# gyrotestbench.net
KiCad netlist of a schematic drawn in EAGLE
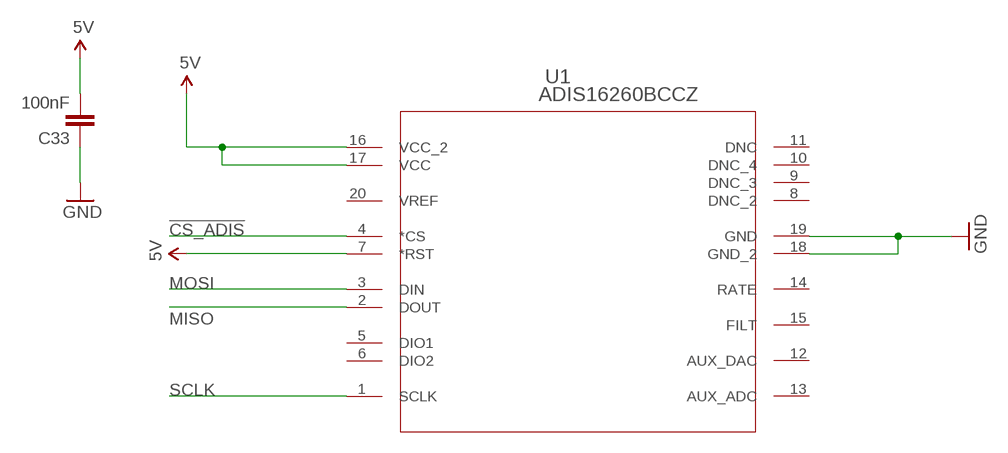
[diagram p0: schematic, sheet 1]
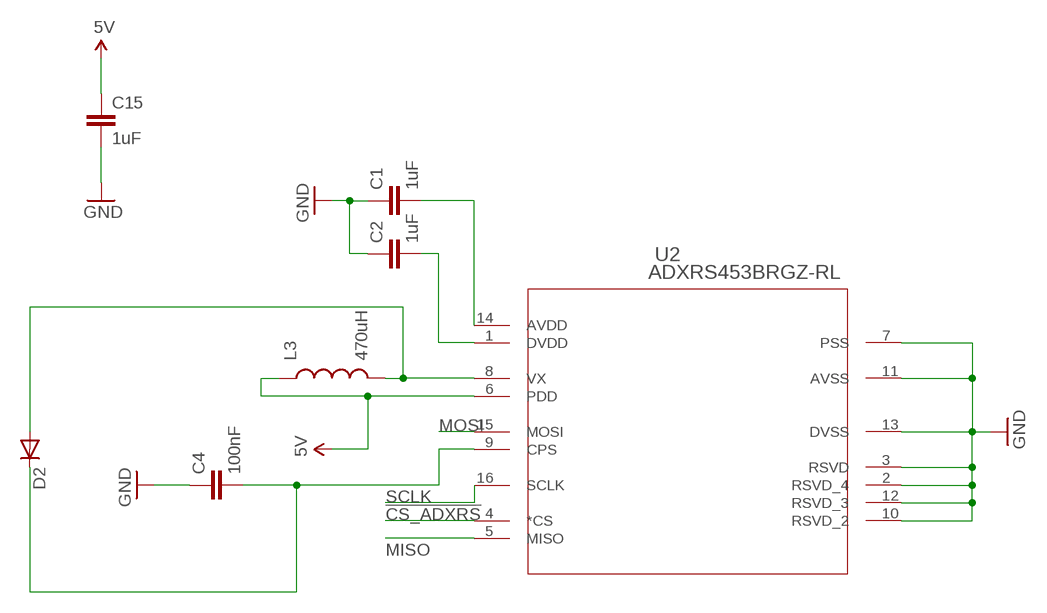
[diagram p1: schematic, sheet 2]
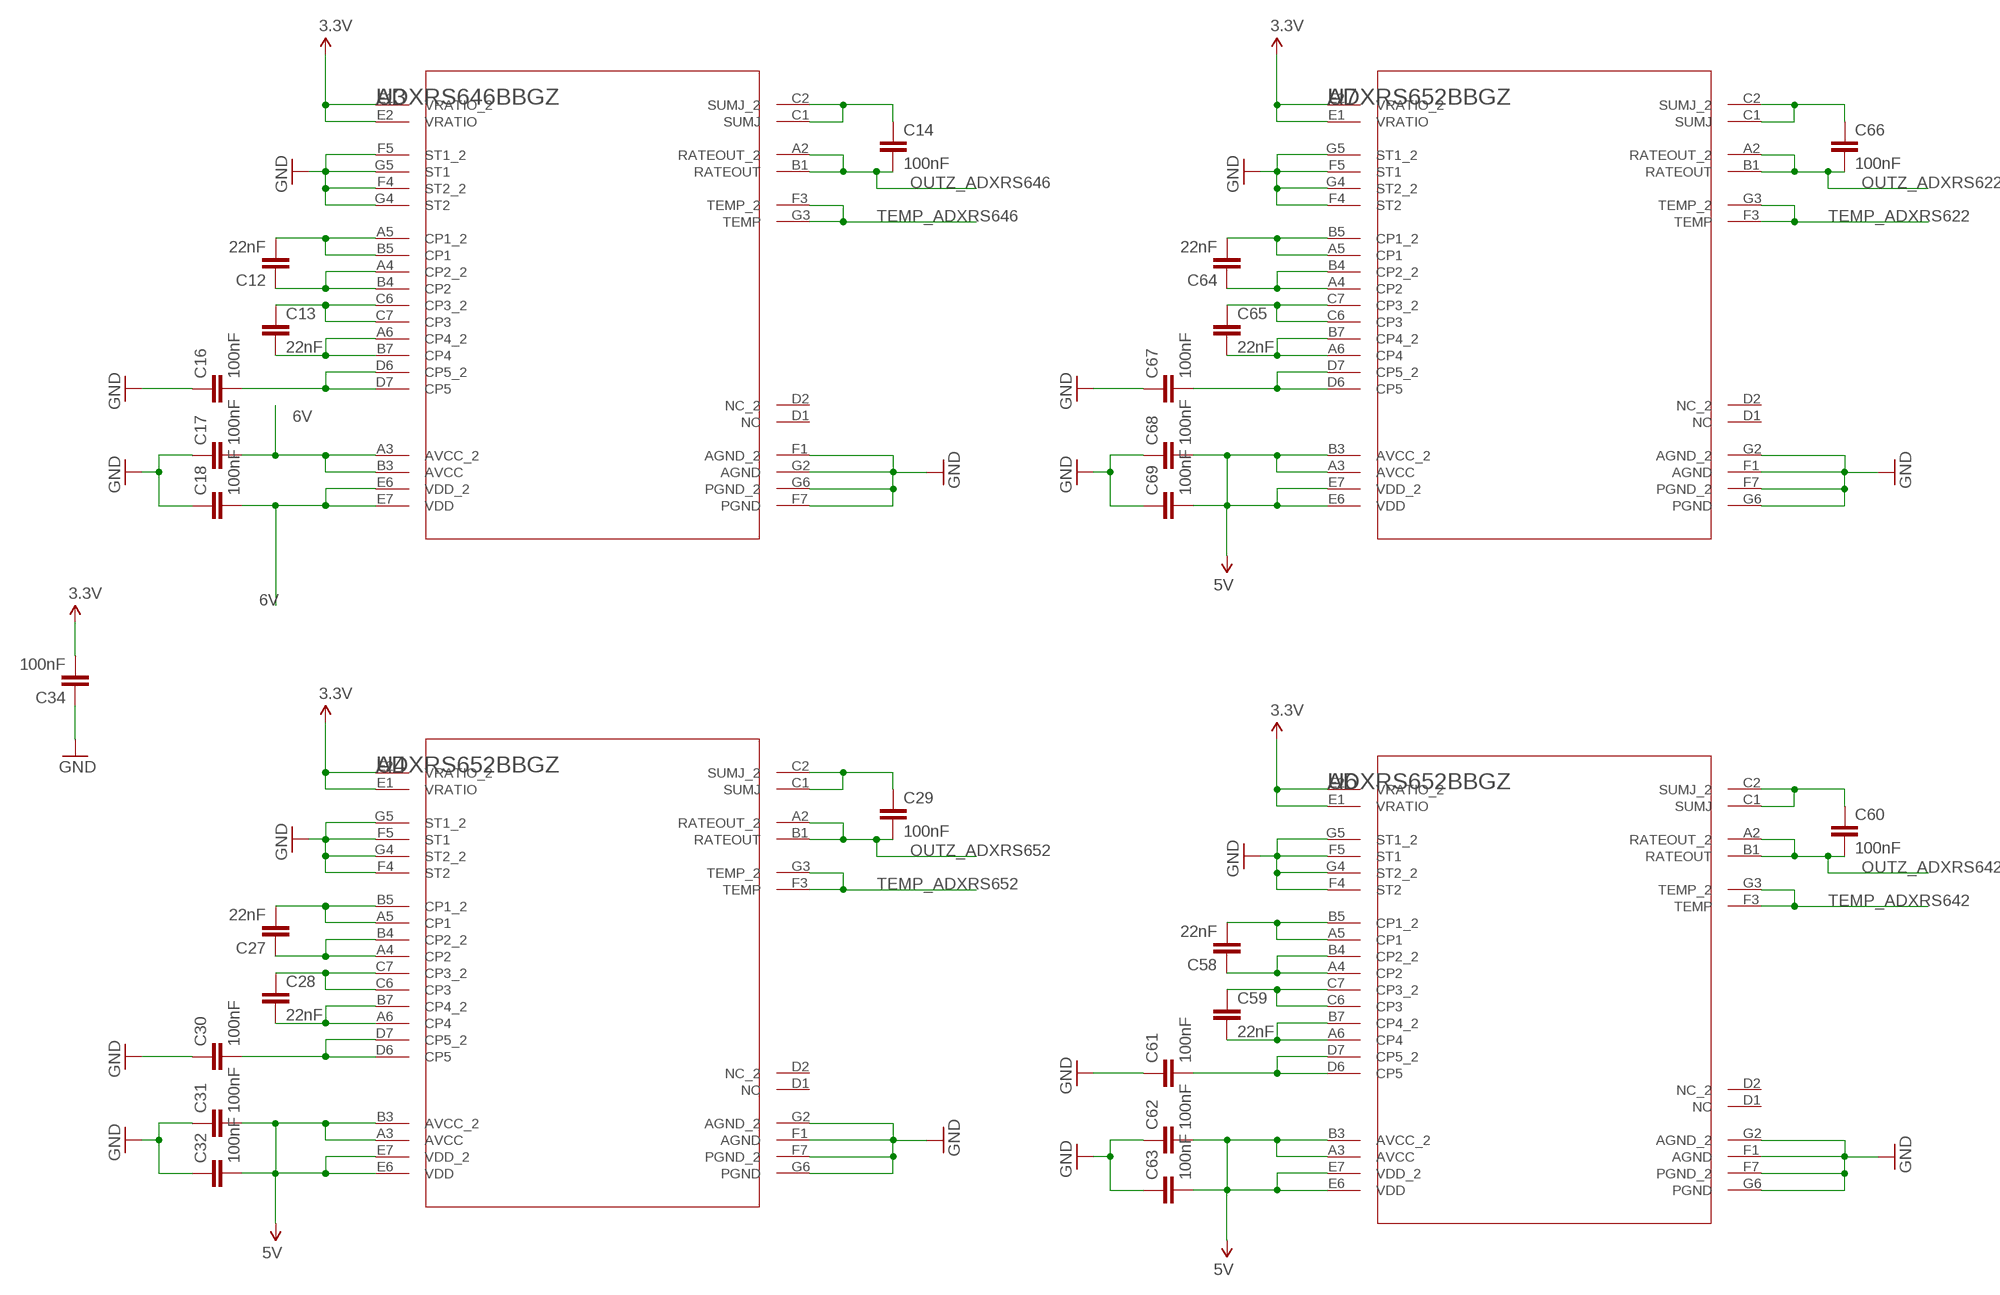
[diagram p2: schematic, sheet 3]
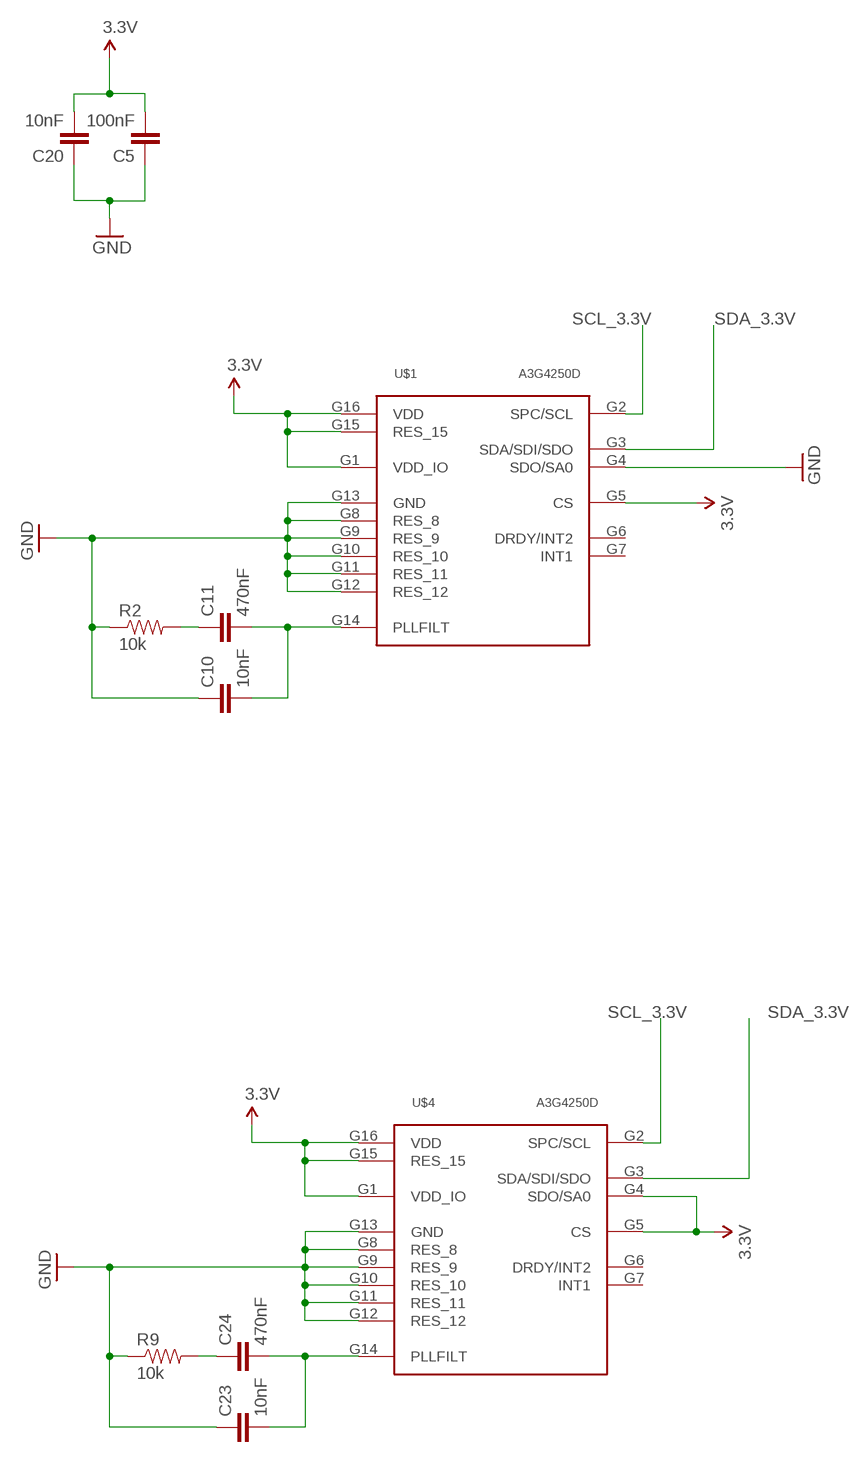
[diagram p3: schematic, sheet 4]
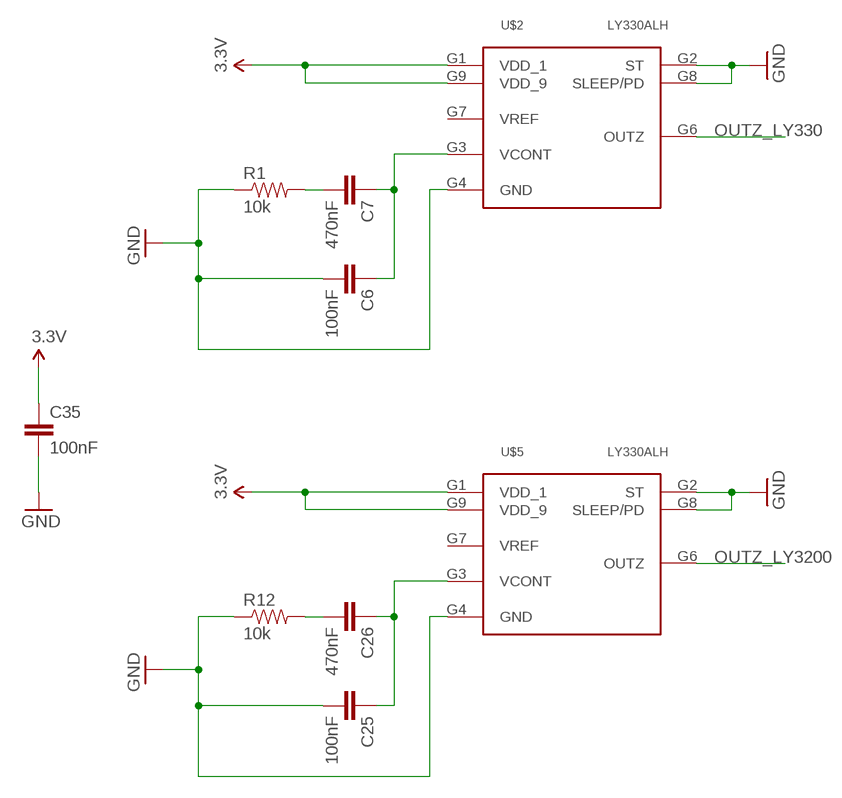
[diagram p4: schematic, sheet 5]
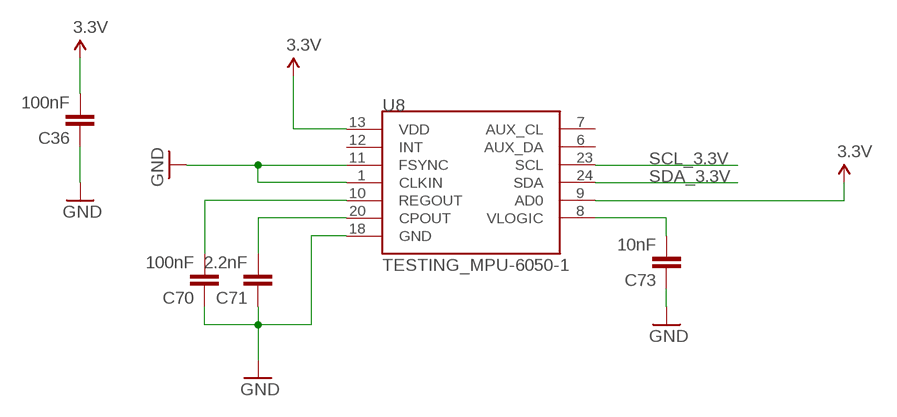
[diagram p5: schematic, sheet 6]
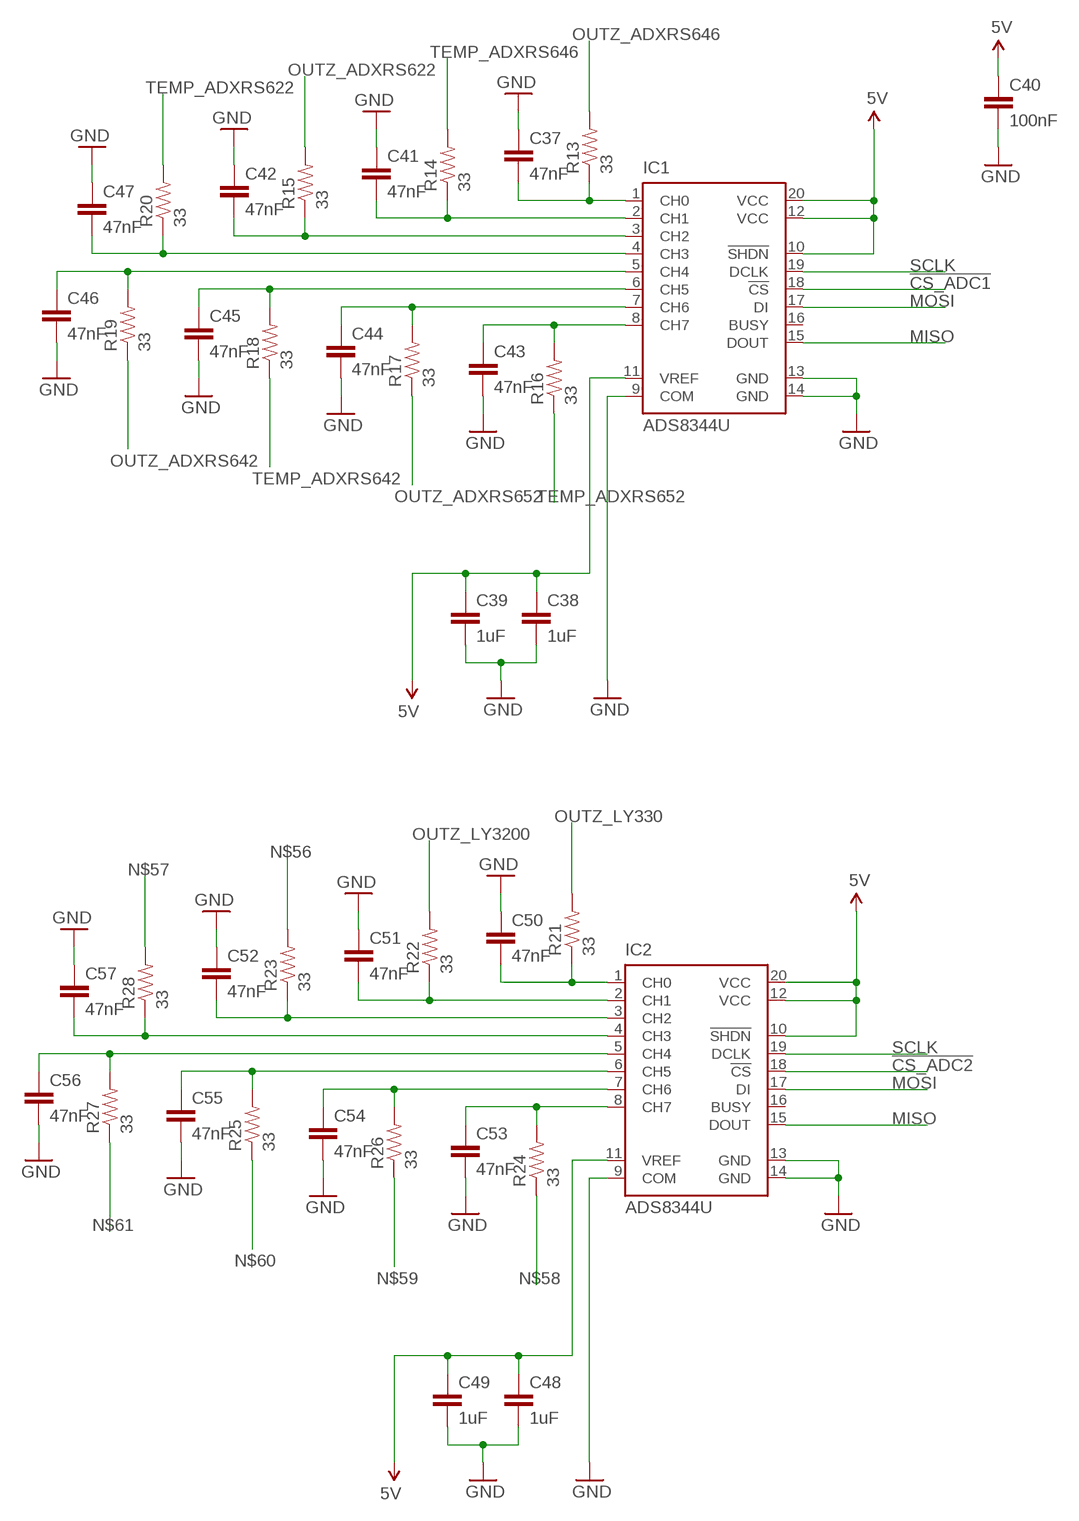
[diagram p6: schematic, sheet 7]
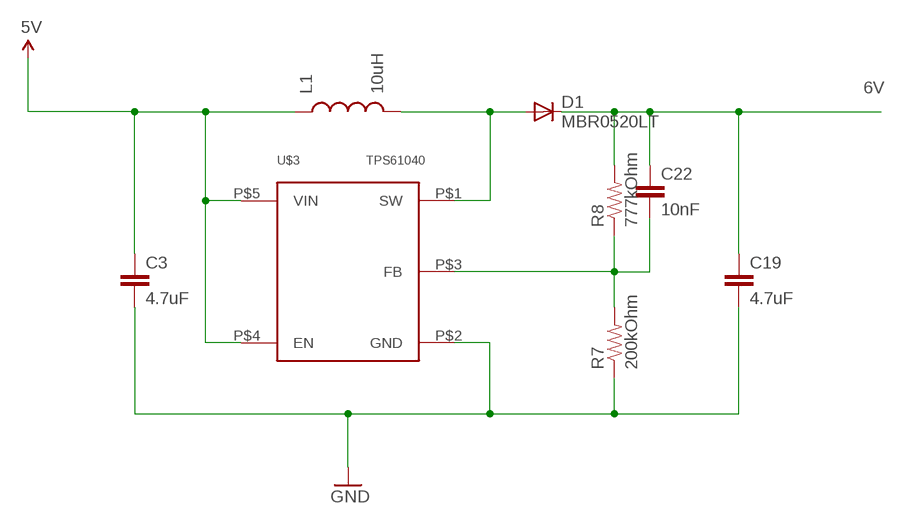
[diagram p7: schematic, sheet 8]
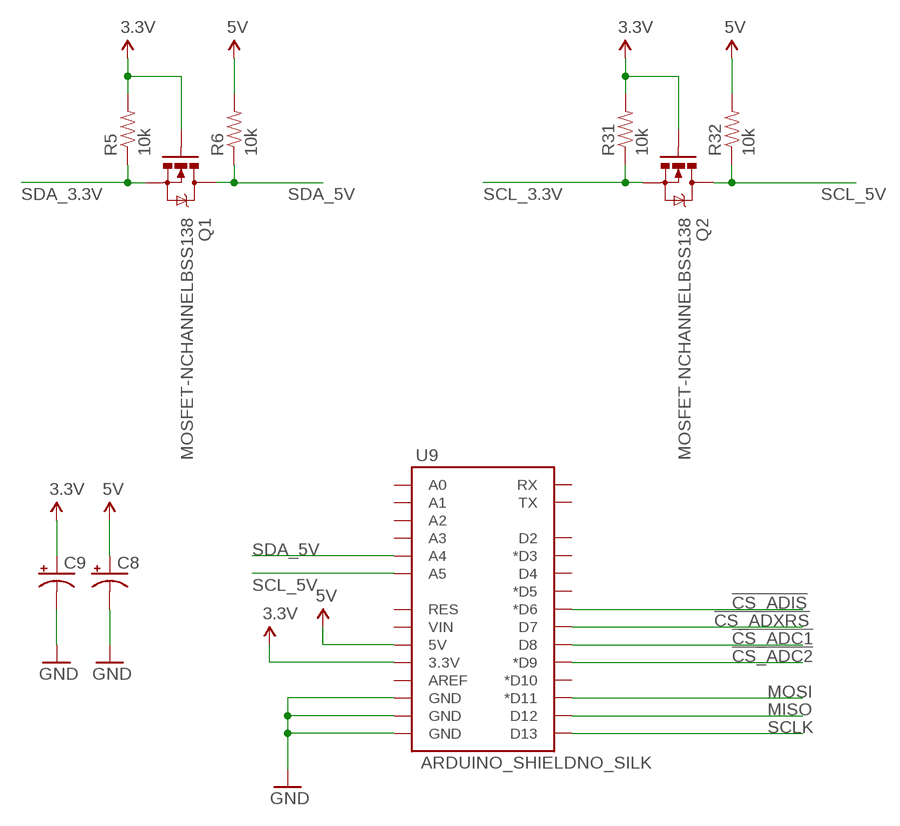
[diagram p8: schematic, sheet 9]

(export (version "E")
  (design (tool "Eeschema 10.0.6"))
  (components
    (comp (ref "C5")
      (value "100nF")
      (footprint "eagle-import:0603-CAP")
      (libsource (lib "eagle-import") (part "CAP0603-CAP"))
    )
    (comp (ref "C10")
      (value "10nF")
      (footprint "eagle-import:0603-CAP")
      (libsource (lib "eagle-import") (part "CAP0603-CAP"))
    )
    (comp (ref "C11")
      (value "470nF")
      (footprint "eagle-import:0603-CAP")
      (libsource (lib "eagle-import") (part "CAP0603-CAP"))
    )
    (comp (ref "C20")
      (value "10nF")
      (footprint "eagle-import:0603-CAP")
      (libsource (lib "eagle-import") (part "CAP0603-CAP"))
    )
    (comp (ref "C23")
      (value "10nF")
      (footprint "eagle-import:0603-CAP")
      (libsource (lib "eagle-import") (part "CAP0603-CAP"))
    )
    (comp (ref "C24")
      (value "470nF")
      (footprint "eagle-import:0603-CAP")
      (libsource (lib "eagle-import") (part "CAP0603-CAP"))
    )
    (comp (ref "R2")
      (value "10k")
      (footprint "eagle-import:0603-RES")
      (libsource (lib "eagle-import") (part "RESISTOR0603-RES"))
    )
    (comp (ref "R9")
      (value "10k")
      (footprint "eagle-import:0603-RES")
      (libsource (lib "eagle-import") (part "RESISTOR0603-RES"))
    )
    (comp (ref "U$1")
      (value "A3G4250D")
      (footprint "eagle-import:LGA-16")
      (libsource (lib "eagle-import") (part "A3G4250D"))
    )
    (comp (ref "U$4")
      (value "A3G4250D")
      (footprint "eagle-import:LGA-16")
      (libsource (lib "eagle-import") (part "A3G4250D"))
    )
    (comp (ref "C8")
      (value "CPOL-USB")
      (footprint "eagle-import:PANASONIC_B")
      (libsource (lib "eagle-import") (part "CPOL-USB"))
    )
    (comp (ref "C9")
      (value "CPOL-USB")
      (footprint "eagle-import:PANASONIC_B")
      (libsource (lib "eagle-import") (part "CPOL-USB"))
    )
    (comp (ref "Q1")
      (value "MOSFET-NCHANNELBSS138")
      (footprint "eagle-import:SOT23")
      (libsource (lib "eagle-import") (part "MOSFET-NCHANNELBSS138"))
    )
    (comp (ref "Q2")
      (value "MOSFET-NCHANNELBSS138")
      (footprint "eagle-import:SOT23")
      (libsource (lib "eagle-import") (part "MOSFET-NCHANNELBSS138"))
    )
    (comp (ref "R5")
      (value "10k")
      (footprint "eagle-import:0603-RES")
      (libsource (lib "eagle-import") (part "RESISTOR0603-RES"))
    )
    (comp (ref "R6")
      (value "10k")
      (footprint "eagle-import:0603-RES")
      (libsource (lib "eagle-import") (part "RESISTOR0603-RES"))
    )
    (comp (ref "R31")
      (value "10k")
      (footprint "eagle-import:0603-RES")
      (libsource (lib "eagle-import") (part "RESISTOR0603-RES"))
    )
    (comp (ref "R32")
      (value "10k")
      (footprint "eagle-import:0603-RES")
      (libsource (lib "eagle-import") (part "RESISTOR0603-RES"))
    )
    (comp (ref "U9")
      (value "ARDUINO_SHIELDNO_SILK")
      (footprint "eagle-import:DUEMILANOVE_VIAS")
      (libsource (lib "eagle-import") (part "ARDUINO_SHIELDNO_SILK"))
    )
    (comp (ref "C1")
      (value "1uF")
      (footprint "eagle-import:0603-CAP")
      (libsource (lib "eagle-import") (part "CAP0603-CAP"))
    )
    (comp (ref "C2")
      (value "1uF")
      (footprint "eagle-import:0603-CAP")
      (libsource (lib "eagle-import") (part "CAP0603-CAP"))
    )
    (comp (ref "C4")
      (value "100nF")
      (footprint "eagle-import:0603-CAP")
      (libsource (lib "eagle-import") (part "CAP0603-CAP"))
    )
    (comp (ref "C15")
      (value "1uF")
      (footprint "eagle-import:0603-CAP")
      (libsource (lib "eagle-import") (part "CAP0603-CAP"))
    )
    (comp (ref "D2")
      (value "DIODEPTH")
      (footprint "eagle-import:DIODE-1N4001")
      (libsource (lib "eagle-import") (part "DIODEPTH"))
    )
    (comp (ref "L3")
      (value "470uH")
      (footprint "eagle-import:1210")
      (libsource (lib "eagle-import") (part "INDUCTOR1210"))
    )
    (comp (ref "U2")
      (value "ADXRS453BRGZ-RL")
      (footprint "eagle-import:RG_16_1")
      (libsource (lib "eagle-import") (part "ADXRS453BRGZ-RL"))
    )
    (comp (ref "C36")
      (value "100nF")
      (footprint "eagle-import:0603-CAP")
      (libsource (lib "eagle-import") (part "CAP0603-CAP"))
    )
    (comp (ref "C70")
      (value "100nF")
      (footprint "eagle-import:0603-CAP")
      (libsource (lib "eagle-import") (part "CAP0603-CAP"))
    )
    (comp (ref "C71")
      (value "2.2nF")
      (footprint "eagle-import:0603-CAP")
      (libsource (lib "eagle-import") (part "CAP0603-CAP"))
    )
    (comp (ref "C73")
      (value "10nF")
      (footprint "eagle-import:0603-CAP")
      (libsource (lib "eagle-import") (part "CAP0603-CAP"))
    )
    (comp (ref "U8")
      (value "TESTING_MPU-6050-1")
      (footprint "eagle-import:TESTING_QFN-24-4MM2")
      (libsource (lib "eagle-import") (part "TESTING_MPU-6050-1"))
    )
    (comp (ref "C37")
      (value "47nF")
      (footprint "eagle-import:0603-CAP")
      (libsource (lib "eagle-import") (part "CAP0603-CAP"))
    )
    (comp (ref "C38")
      (value "1uF")
      (footprint "eagle-import:0603-CAP")
      (libsource (lib "eagle-import") (part "CAP0603-CAP"))
    )
    (comp (ref "C39")
      (value "1uF")
      (footprint "eagle-import:0603-CAP")
      (libsource (lib "eagle-import") (part "CAP0603-CAP"))
    )
    (comp (ref "C40")
      (value "100nF")
      (footprint "eagle-import:0603-CAP")
      (libsource (lib "eagle-import") (part "CAP0603-CAP"))
    )
    (comp (ref "C41")
      (value "47nF")
      (footprint "eagle-import:0603-CAP")
      (libsource (lib "eagle-import") (part "CAP0603-CAP"))
    )
    (comp (ref "C42")
      (value "47nF")
      (footprint "eagle-import:0603-CAP")
      (libsource (lib "eagle-import") (part "CAP0603-CAP"))
    )
    (comp (ref "C43")
      (value "47nF")
      (footprint "eagle-import:0603-CAP")
      (libsource (lib "eagle-import") (part "CAP0603-CAP"))
    )
    (comp (ref "C44")
      (value "47nF")
      (footprint "eagle-import:0603-CAP")
      (libsource (lib "eagle-import") (part "CAP0603-CAP"))
    )
    (comp (ref "C45")
      (value "47nF")
      (footprint "eagle-import:0603-CAP")
      (libsource (lib "eagle-import") (part "CAP0603-CAP"))
    )
    (comp (ref "C46")
      (value "47nF")
      (footprint "eagle-import:0603-CAP")
      (libsource (lib "eagle-import") (part "CAP0603-CAP"))
    )
    (comp (ref "C47")
      (value "47nF")
      (footprint "eagle-import:0603-CAP")
      (libsource (lib "eagle-import") (part "CAP0603-CAP"))
    )
    (comp (ref "C48")
      (value "1uF")
      (footprint "eagle-import:0603-CAP")
      (libsource (lib "eagle-import") (part "CAP0603-CAP"))
    )
    (comp (ref "C49")
      (value "1uF")
      (footprint "eagle-import:0603-CAP")
      (libsource (lib "eagle-import") (part "CAP0603-CAP"))
    )
    (comp (ref "C50")
      (value "47nF")
      (footprint "eagle-import:0603-CAP")
      (libsource (lib "eagle-import") (part "CAP0603-CAP"))
    )
    (comp (ref "C51")
      (value "47nF")
      (footprint "eagle-import:0603-CAP")
      (libsource (lib "eagle-import") (part "CAP0603-CAP"))
    )
    (comp (ref "C52")
      (value "47nF")
      (footprint "eagle-import:0603-CAP")
      (libsource (lib "eagle-import") (part "CAP0603-CAP"))
    )
    (comp (ref "C53")
      (value "47nF")
      (footprint "eagle-import:0603-CAP")
      (libsource (lib "eagle-import") (part "CAP0603-CAP"))
    )
    (comp (ref "C54")
      (value "47nF")
      (footprint "eagle-import:0603-CAP")
      (libsource (lib "eagle-import") (part "CAP0603-CAP"))
    )
    (comp (ref "C55")
      (value "47nF")
      (footprint "eagle-import:0603-CAP")
      (libsource (lib "eagle-import") (part "CAP0603-CAP"))
    )
    (comp (ref "C56")
      (value "47nF")
      (footprint "eagle-import:0603-CAP")
      (libsource (lib "eagle-import") (part "CAP0603-CAP"))
    )
    (comp (ref "C57")
      (value "47nF")
      (footprint "eagle-import:0603-CAP")
      (libsource (lib "eagle-import") (part "CAP0603-CAP"))
    )
    (comp (ref "IC1")
      (value "ADS8344U")
      (footprint "eagle-import:SSOP20BU")
      (fields (field (name "MPN") "ADS8344NB"))
      (libsource (lib "eagle-import") (part "ADS8344U"))
    )
    (comp (ref "IC2")
      (value "ADS8344U")
      (footprint "eagle-import:SSOP20BU")
      (fields (field (name "MPN") "ADS8344NB"))
      (libsource (lib "eagle-import") (part "ADS8344U"))
    )
    (comp (ref "R13")
      (value "33")
      (footprint "eagle-import:0603-RES")
      (libsource (lib "eagle-import") (part "RESISTOR0603-RES"))
    )
    (comp (ref "R14")
      (value "33")
      (footprint "eagle-import:0603-RES")
      (libsource (lib "eagle-import") (part "RESISTOR0603-RES"))
    )
    (comp (ref "R15")
      (value "33")
      (footprint "eagle-import:0603-RES")
      (libsource (lib "eagle-import") (part "RESISTOR0603-RES"))
    )
    (comp (ref "R16")
      (value "33")
      (footprint "eagle-import:0603-RES")
      (libsource (lib "eagle-import") (part "RESISTOR0603-RES"))
    )
    (comp (ref "R17")
      (value "33")
      (footprint "eagle-import:0603-RES")
      (libsource (lib "eagle-import") (part "RESISTOR0603-RES"))
    )
    (comp (ref "R18")
      (value "33")
      (footprint "eagle-import:0603-RES")
      (libsource (lib "eagle-import") (part "RESISTOR0603-RES"))
    )
    (comp (ref "R19")
      (value "33")
      (footprint "eagle-import:0603-RES")
      (libsource (lib "eagle-import") (part "RESISTOR0603-RES"))
    )
    (comp (ref "R20")
      (value "33")
      (footprint "eagle-import:0603-RES")
      (libsource (lib "eagle-import") (part "RESISTOR0603-RES"))
    )
    (comp (ref "R21")
      (value "33")
      (footprint "eagle-import:0603-RES")
      (libsource (lib "eagle-import") (part "RESISTOR0603-RES"))
    )
    (comp (ref "R22")
      (value "33")
      (footprint "eagle-import:0603-RES")
      (libsource (lib "eagle-import") (part "RESISTOR0603-RES"))
    )
    (comp (ref "R23")
      (value "33")
      (footprint "eagle-import:0603-RES")
      (libsource (lib "eagle-import") (part "RESISTOR0603-RES"))
    )
    (comp (ref "R24")
      (value "33")
      (footprint "eagle-import:0603-RES")
      (libsource (lib "eagle-import") (part "RESISTOR0603-RES"))
    )
    (comp (ref "R25")
      (value "33")
      (footprint "eagle-import:0603-RES")
      (libsource (lib "eagle-import") (part "RESISTOR0603-RES"))
    )
    (comp (ref "R26")
      (value "33")
      (footprint "eagle-import:0603-RES")
      (libsource (lib "eagle-import") (part "RESISTOR0603-RES"))
    )
    (comp (ref "R27")
      (value "33")
      (footprint "eagle-import:0603-RES")
      (libsource (lib "eagle-import") (part "RESISTOR0603-RES"))
    )
    (comp (ref "R28")
      (value "33")
      (footprint "eagle-import:0603-RES")
      (libsource (lib "eagle-import") (part "RESISTOR0603-RES"))
    )
    (comp (ref "C6")
      (value "100nF")
      (footprint "eagle-import:0603-CAP")
      (libsource (lib "eagle-import") (part "CAP0603-CAP"))
    )
    (comp (ref "C7")
      (value "470nF")
      (footprint "eagle-import:0603-CAP")
      (libsource (lib "eagle-import") (part "CAP0603-CAP"))
    )
    (comp (ref "C25")
      (value "100nF")
      (footprint "eagle-import:0603-CAP")
      (libsource (lib "eagle-import") (part "CAP0603-CAP"))
    )
    (comp (ref "C26")
      (value "470nF")
      (footprint "eagle-import:0603-CAP")
      (libsource (lib "eagle-import") (part "CAP0603-CAP"))
    )
    (comp (ref "C35")
      (value "100nF")
      (footprint "eagle-import:0603-CAP")
      (libsource (lib "eagle-import") (part "CAP0603-CAP"))
    )
    (comp (ref "R1")
      (value "10k")
      (footprint "eagle-import:0603-RES")
      (libsource (lib "eagle-import") (part "RESISTOR0603-RES"))
    )
    (comp (ref "R12")
      (value "10k")
      (footprint "eagle-import:0603-RES")
      (libsource (lib "eagle-import") (part "RESISTOR0603-RES"))
    )
    (comp (ref "U$2")
      (value "LY330ALH")
      (footprint "eagle-import:LGA-10")
      (libsource (lib "eagle-import") (part "LY330ALH"))
    )
    (comp (ref "U$5")
      (value "LY330ALH")
      (footprint "eagle-import:LGA-10")
      (libsource (lib "eagle-import") (part "LY330ALH"))
    )
    (comp (ref "C3")
      (value "4.7uF")
      (footprint "eagle-import:0603-CAP")
      (libsource (lib "eagle-import") (part "CAP0603-CAP"))
    )
    (comp (ref "C19")
      (value "4.7uF")
      (footprint "eagle-import:0603-CAP")
      (libsource (lib "eagle-import") (part "CAP0603-CAP"))
    )
    (comp (ref "C22")
      (value "10nF")
      (footprint "eagle-import:0603-CAP")
      (libsource (lib "eagle-import") (part "CAP0603-CAP"))
    )
    (comp (ref "D1")
      (value "MBR0520LT")
      (footprint "eagle-import:SOD123")
      (libsource (lib "eagle-import") (part "MBR0520LT"))
    )
    (comp (ref "L1")
      (value "10uH")
      (footprint "eagle-import:1210")
      (libsource (lib "eagle-import") (part "INDUCTOR1210"))
    )
    (comp (ref "R7")
      (value "200kOhm")
      (footprint "eagle-import:0603-RES")
      (libsource (lib "eagle-import") (part "RESISTOR0603-RES"))
    )
    (comp (ref "R8")
      (value "777kOhm")
      (footprint "eagle-import:0603-RES")
      (libsource (lib "eagle-import") (part "RESISTOR0603-RES"))
    )
    (comp (ref "U$3")
      (value "TPS61040")
      (footprint "eagle-import:DBV")
      (libsource (lib "eagle-import") (part "TPS61040"))
    )
    (comp (ref "C33")
      (value "100nF")
      (footprint "eagle-import:0603-CAP")
      (libsource (lib "eagle-import") (part "CAP0603-CAP"))
    )
    (comp (ref "U1")
      (value "ADIS16260BCCZ")
      (footprint "eagle-import:LGA_CC-20-1")
      (libsource (lib "eagle-import") (part "ADIS16260BCCZ"))
    )
    (comp (ref "C12")
      (value "22nF")
      (footprint "eagle-import:0603-CAP")
      (libsource (lib "eagle-import") (part "CAP0603-CAP"))
    )
    (comp (ref "C13")
      (value "22nF")
      (footprint "eagle-import:0603-CAP")
      (libsource (lib "eagle-import") (part "CAP0603-CAP"))
    )
    (comp (ref "C14")
      (value "100nF")
      (footprint "eagle-import:0603-CAP")
      (libsource (lib "eagle-import") (part "CAP0603-CAP"))
    )
    (comp (ref "C16")
      (value "100nF")
      (footprint "eagle-import:0603-CAP")
      (libsource (lib "eagle-import") (part "CAP0603-CAP"))
    )
    (comp (ref "C17")
      (value "100nF")
      (footprint "eagle-import:0603-CAP")
      (libsource (lib "eagle-import") (part "CAP0603-CAP"))
    )
    (comp (ref "C18")
      (value "100nF")
      (footprint "eagle-import:0603-CAP")
      (libsource (lib "eagle-import") (part "CAP0603-CAP"))
    )
    (comp (ref "C27")
      (value "22nF")
      (footprint "eagle-import:0603-CAP")
      (libsource (lib "eagle-import") (part "CAP0603-CAP"))
    )
    (comp (ref "C28")
      (value "22nF")
      (footprint "eagle-import:0603-CAP")
      (libsource (lib "eagle-import") (part "CAP0603-CAP"))
    )
    (comp (ref "C29")
      (value "100nF")
      (footprint "eagle-import:0603-CAP")
      (libsource (lib "eagle-import") (part "CAP0603-CAP"))
    )
    (comp (ref "C30")
      (value "100nF")
      (footprint "eagle-import:0603-CAP")
      (libsource (lib "eagle-import") (part "CAP0603-CAP"))
    )
    (comp (ref "C31")
      (value "100nF")
      (footprint "eagle-import:0603-CAP")
      (libsource (lib "eagle-import") (part "CAP0603-CAP"))
    )
    (comp (ref "C32")
      (value "100nF")
      (footprint "eagle-import:0603-CAP")
      (libsource (lib "eagle-import") (part "CAP0603-CAP"))
    )
    (comp (ref "C34")
      (value "100nF")
      (footprint "eagle-import:0603-CAP")
      (libsource (lib "eagle-import") (part "CAP0603-CAP"))
    )
    (comp (ref "C58")
      (value "22nF")
      (footprint "eagle-import:0603-CAP")
      (libsource (lib "eagle-import") (part "CAP0603-CAP"))
    )
    (comp (ref "C59")
      (value "22nF")
      (footprint "eagle-import:0603-CAP")
      (libsource (lib "eagle-import") (part "CAP0603-CAP"))
    )
    (comp (ref "C60")
      (value "100nF")
      (footprint "eagle-import:0603-CAP")
      (libsource (lib "eagle-import") (part "CAP0603-CAP"))
    )
    (comp (ref "C61")
      (value "100nF")
      (footprint "eagle-import:0603-CAP")
      (libsource (lib "eagle-import") (part "CAP0603-CAP"))
    )
    (comp (ref "C62")
      (value "100nF")
      (footprint "eagle-import:0603-CAP")
      (libsource (lib "eagle-import") (part "CAP0603-CAP"))
    )
    (comp (ref "C63")
      (value "100nF")
      (footprint "eagle-import:0603-CAP")
      (libsource (lib "eagle-import") (part "CAP0603-CAP"))
    )
    (comp (ref "C64")
      (value "22nF")
      (footprint "eagle-import:0603-CAP")
      (libsource (lib "eagle-import") (part "CAP0603-CAP"))
    )
    (comp (ref "C65")
      (value "22nF")
      (footprint "eagle-import:0603-CAP")
      (libsource (lib "eagle-import") (part "CAP0603-CAP"))
    )
    (comp (ref "C66")
      (value "100nF")
      (footprint "eagle-import:0603-CAP")
      (libsource (lib "eagle-import") (part "CAP0603-CAP"))
    )
    (comp (ref "C67")
      (value "100nF")
      (footprint "eagle-import:0603-CAP")
      (libsource (lib "eagle-import") (part "CAP0603-CAP"))
    )
    (comp (ref "C68")
      (value "100nF")
      (footprint "eagle-import:0603-CAP")
      (libsource (lib "eagle-import") (part "CAP0603-CAP"))
    )
    (comp (ref "C69")
      (value "100nF")
      (footprint "eagle-import:0603-CAP")
      (libsource (lib "eagle-import") (part "CAP0603-CAP"))
    )
    (comp (ref "U3")
      (value "ADXRS646BBGZ")
      (footprint "eagle-import:BG_32_3")
      (fields (field (name "MANUFACTURER_PART_NUMBER") "ADXRS613BBGZ"))
      (libsource (lib "eagle-import") (part "ADXRS646BBGZ"))
    )
    (comp (ref "U4")
      (value "ADXRS652BBGZ")
      (footprint "eagle-import:BG_32_3")
      (libsource (lib "eagle-import") (part "ADXRS652BBGZ"))
    )
    (comp (ref "U6")
      (value "ADXRS652BBGZ")
      (footprint "eagle-import:BG_32_3")
      (libsource (lib "eagle-import") (part "ADXRS652BBGZ"))
    )
    (comp (ref "U7")
      (value "ADXRS652BBGZ")
      (footprint "eagle-import:BG_32_3")
      (libsource (lib "eagle-import") (part "ADXRS652BBGZ"))
    )
  )
  (nets
    (net (code "1") (name "3.3V") (class "Default")
      (node (ref "C20") (pin "2") (pinfunction "2_2") (pintype "passive"))
      (node (ref "C34") (pin "2") (pinfunction "2_2") (pintype "passive"))
      (node (ref "C35") (pin "1") (pinfunction "1_1") (pintype "passive"))
      (node (ref "C36") (pin "2") (pinfunction "2_2") (pintype "passive"))
      (node (ref "C5") (pin "2") (pinfunction "2_2") (pintype "passive"))
      (node (ref "C9") (pin "+") (pinfunction "+_+") (pintype "passive"))
      (node (ref "Q1") (pin "1") (pinfunction "G_1") (pintype "passive"))
      (node (ref "Q2") (pin "1") (pinfunction "G_1") (pintype "passive"))
      (node (ref "R31") (pin "2") (pinfunction "2_2") (pintype "passive"))
      (node (ref "R5") (pin "2") (pinfunction "2_2") (pintype "passive"))
      (node (ref "U$1") (pin "G1") (pinfunction "VDD_IO_G1") (pintype "bidirectional"))
      (node (ref "U$1") (pin "G15") (pinfunction "RES_15_G15") (pintype "bidirectional"))
      (node (ref "U$1") (pin "G16") (pinfunction "VDD_G16") (pintype "bidirectional"))
      (node (ref "U$1") (pin "G5") (pinfunction "CS_G5") (pintype "bidirectional"))
      (node (ref "U$2") (pin "G1") (pinfunction "VDD_1_G1") (pintype "bidirectional"))
      (node (ref "U$2") (pin "G9") (pinfunction "VDD_9_G9") (pintype "bidirectional"))
      (node (ref "U$4") (pin "G1") (pinfunction "VDD_IO_G1") (pintype "bidirectional"))
      (node (ref "U$4") (pin "G15") (pinfunction "RES_15_G15") (pintype "bidirectional"))
      (node (ref "U$4") (pin "G16") (pinfunction "VDD_G16") (pintype "bidirectional"))
      (node (ref "U$4") (pin "G4") (pinfunction "SDO/SA0_G4") (pintype "bidirectional"))
      (node (ref "U$4") (pin "G5") (pinfunction "CS_G5") (pintype "bidirectional"))
      (node (ref "U$5") (pin "G1") (pinfunction "VDD_1_G1") (pintype "bidirectional"))
      (node (ref "U$5") (pin "G9") (pinfunction "VDD_9_G9") (pintype "bidirectional"))
      (node (ref "U3") (pin "E1") (pinfunction "VRATIO_2_E1") (pintype "power_in"))
      (node (ref "U3") (pin "E2") (pinfunction "VRATIO_E2") (pintype "power_in"))
      (node (ref "U4") (pin "E1") (pinfunction "VRATIO_E1") (pintype "power_in"))
      (node (ref "U4") (pin "E2") (pinfunction "VRATIO_2_E2") (pintype "power_in"))
      (node (ref "U6") (pin "E1") (pinfunction "VRATIO_E1") (pintype "power_in"))
      (node (ref "U6") (pin "E2") (pinfunction "VRATIO_2_E2") (pintype "power_in"))
      (node (ref "U7") (pin "E1") (pinfunction "VRATIO_E1") (pintype "power_in"))
      (node (ref "U7") (pin "E2") (pinfunction "VRATIO_2_E2") (pintype "power_in"))
      (node (ref "U8") (pin "13") (pinfunction "VDD_13") (pintype "bidirectional"))
      (node (ref "U8") (pin "9") (pinfunction "AD0_9") (pintype "bidirectional"))
      (node (ref "U9") (pin "3.3V") (pinfunction "3.3V_3.3V") (pintype "bidirectional"))
    )
    (net (code "2") (name "5V") (class "Default")
      (node (ref "C15") (pin "1") (pinfunction "1_1") (pintype "passive"))
      (node (ref "C3") (pin "1") (pinfunction "1_1") (pintype "passive"))
      (node (ref "C31") (pin "2") (pinfunction "2_2") (pintype "passive"))
      (node (ref "C32") (pin "2") (pinfunction "2_2") (pintype "passive"))
      (node (ref "C33") (pin "2") (pinfunction "2_2") (pintype "passive"))
      (node (ref "C38") (pin "1") (pinfunction "1_1") (pintype "passive"))
      (node (ref "C39") (pin "1") (pinfunction "1_1") (pintype "passive"))
      (node (ref "C40") (pin "1") (pinfunction "1_1") (pintype "passive"))
      (node (ref "C48") (pin "1") (pinfunction "1_1") (pintype "passive"))
      (node (ref "C49") (pin "1") (pinfunction "1_1") (pintype "passive"))
      (node (ref "C62") (pin "2") (pinfunction "2_2") (pintype "passive"))
      (node (ref "C63") (pin "2") (pinfunction "2_2") (pintype "passive"))
      (node (ref "C68") (pin "2") (pinfunction "2_2") (pintype "passive"))
      (node (ref "C69") (pin "2") (pinfunction "2_2") (pintype "passive"))
      (node (ref "C8") (pin "+") (pinfunction "+_+") (pintype "passive"))
      (node (ref "IC1") (pin "10") (pinfunction "~{SHDN}_10") (pintype "input"))
      (node (ref "IC1") (pin "11") (pinfunction "VREF_11") (pintype "input"))
      (node (ref "IC1") (pin "12") (pinfunction "VCC_12") (pintype "power_in"))
      (node (ref "IC1") (pin "20") (pinfunction "VCC_20") (pintype "power_in"))
      (node (ref "IC2") (pin "10") (pinfunction "~{SHDN}_10") (pintype "input"))
      (node (ref "IC2") (pin "11") (pinfunction "VREF_11") (pintype "input"))
      (node (ref "IC2") (pin "12") (pinfunction "VCC_12") (pintype "power_in"))
      (node (ref "IC2") (pin "20") (pinfunction "VCC_20") (pintype "power_in"))
      (node (ref "L1") (pin "1") (pinfunction "1_1") (pintype "passive"))
      (node (ref "L3") (pin "1") (pinfunction "1_1") (pintype "passive"))
      (node (ref "R32") (pin "2") (pinfunction "2_2") (pintype "passive"))
      (node (ref "R6") (pin "2") (pinfunction "2_2") (pintype "passive"))
      (node (ref "U$3") (pin "P$4") (pinfunction "EN_P$4") (pintype "bidirectional"))
      (node (ref "U$3") (pin "P$5") (pinfunction "VIN_P$5") (pintype "bidirectional"))
      (node (ref "U1") (pin "16") (pinfunction "VCC_2_16") (pintype "passive"))
      (node (ref "U1") (pin "17") (pinfunction "VCC_17") (pintype "passive"))
      (node (ref "U1") (pin "7") (pinfunction "*RST_7") (pintype "passive"))
      (node (ref "U2") (pin "6") (pinfunction "PDD_6") (pintype "passive"))
      (node (ref "U4") (pin "A3") (pinfunction "AVCC_A3") (pintype "power_in"))
      (node (ref "U4") (pin "B3") (pinfunction "AVCC_2_B3") (pintype "power_in"))
      (node (ref "U4") (pin "E6") (pinfunction "VDD_E6") (pintype "power_in"))
      (node (ref "U4") (pin "E7") (pinfunction "VDD_2_E7") (pintype "power_in"))
      (node (ref "U6") (pin "A3") (pinfunction "AVCC_A3") (pintype "power_in"))
      (node (ref "U6") (pin "B3") (pinfunction "AVCC_2_B3") (pintype "power_in"))
      (node (ref "U6") (pin "E6") (pinfunction "VDD_E6") (pintype "power_in"))
      (node (ref "U6") (pin "E7") (pinfunction "VDD_2_E7") (pintype "power_in"))
      (node (ref "U7") (pin "A3") (pinfunction "AVCC_A3") (pintype "power_in"))
      (node (ref "U7") (pin "B3") (pinfunction "AVCC_2_B3") (pintype "power_in"))
      (node (ref "U7") (pin "E6") (pinfunction "VDD_E6") (pintype "power_in"))
      (node (ref "U7") (pin "E7") (pinfunction "VDD_2_E7") (pintype "power_in"))
      (node (ref "U9") (pin "5V") (pinfunction "5V_5V") (pintype "bidirectional"))
    )
    (net (code "3") (name "6V") (class "Default")
      (node (ref "C17") (pin "2") (pinfunction "2_2") (pintype "passive"))
      (node (ref "C18") (pin "2") (pinfunction "2_2") (pintype "passive"))
      (node (ref "C19") (pin "1") (pinfunction "1_1") (pintype "passive"))
      (node (ref "C22") (pin "1") (pinfunction "1_1") (pintype "passive"))
      (node (ref "D1") (pin "C") (pinfunction "C_C") (pintype "passive"))
      (node (ref "R8") (pin "2") (pinfunction "2_2") (pintype "passive"))
      (node (ref "U3") (pin "A3") (pinfunction "AVCC_2_A3") (pintype "power_in"))
      (node (ref "U3") (pin "B3") (pinfunction "AVCC_B3") (pintype "power_in"))
      (node (ref "U3") (pin "E6") (pinfunction "VDD_2_E6") (pintype "power_in"))
      (node (ref "U3") (pin "E7") (pinfunction "VDD_E7") (pintype "power_in"))
    )
    (net (code "4") (name "GND") (class "Default")
      (node (ref "C1") (pin "1") (pinfunction "1_1") (pintype "passive"))
      (node (ref "C10") (pin "1") (pinfunction "1_1") (pintype "passive"))
      (node (ref "C15") (pin "2") (pinfunction "2_2") (pintype "passive"))
      (node (ref "C16") (pin "1") (pinfunction "1_1") (pintype "passive"))
      (node (ref "C17") (pin "1") (pinfunction "1_1") (pintype "passive"))
      (node (ref "C18") (pin "1") (pinfunction "1_1") (pintype "passive"))
      (node (ref "C19") (pin "2") (pinfunction "2_2") (pintype "passive"))
      (node (ref "C2") (pin "1") (pinfunction "1_1") (pintype "passive"))
      (node (ref "C20") (pin "1") (pinfunction "1_1") (pintype "passive"))
      (node (ref "C23") (pin "1") (pinfunction "1_1") (pintype "passive"))
      (node (ref "C25") (pin "2") (pinfunction "2_2") (pintype "passive"))
      (node (ref "C3") (pin "2") (pinfunction "2_2") (pintype "passive"))
      (node (ref "C30") (pin "1") (pinfunction "1_1") (pintype "passive"))
      (node (ref "C31") (pin "1") (pinfunction "1_1") (pintype "passive"))
      (node (ref "C32") (pin "1") (pinfunction "1_1") (pintype "passive"))
      (node (ref "C33") (pin "1") (pinfunction "1_1") (pintype "passive"))
      (node (ref "C34") (pin "1") (pinfunction "1_1") (pintype "passive"))
      (node (ref "C35") (pin "2") (pinfunction "2_2") (pintype "passive"))
      (node (ref "C36") (pin "1") (pinfunction "1_1") (pintype "passive"))
      (node (ref "C37") (pin "1") (pinfunction "1_1") (pintype "passive"))
      (node (ref "C38") (pin "2") (pinfunction "2_2") (pintype "passive"))
      (node (ref "C39") (pin "2") (pinfunction "2_2") (pintype "passive"))
      (node (ref "C4") (pin "1") (pinfunction "1_1") (pintype "passive"))
      (node (ref "C40") (pin "2") (pinfunction "2_2") (pintype "passive"))
      (node (ref "C41") (pin "1") (pinfunction "1_1") (pintype "passive"))
      (node (ref "C42") (pin "1") (pinfunction "1_1") (pintype "passive"))
      (node (ref "C43") (pin "2") (pinfunction "2_2") (pintype "passive"))
      (node (ref "C44") (pin "2") (pinfunction "2_2") (pintype "passive"))
      (node (ref "C45") (pin "2") (pinfunction "2_2") (pintype "passive"))
      (node (ref "C46") (pin "2") (pinfunction "2_2") (pintype "passive"))
      (node (ref "C47") (pin "1") (pinfunction "1_1") (pintype "passive"))
      (node (ref "C48") (pin "2") (pinfunction "2_2") (pintype "passive"))
      (node (ref "C49") (pin "2") (pinfunction "2_2") (pintype "passive"))
      (node (ref "C5") (pin "1") (pinfunction "1_1") (pintype "passive"))
      (node (ref "C50") (pin "1") (pinfunction "1_1") (pintype "passive"))
      (node (ref "C51") (pin "1") (pinfunction "1_1") (pintype "passive"))
      (node (ref "C52") (pin "1") (pinfunction "1_1") (pintype "passive"))
      (node (ref "C53") (pin "2") (pinfunction "2_2") (pintype "passive"))
      (node (ref "C54") (pin "2") (pinfunction "2_2") (pintype "passive"))
      (node (ref "C55") (pin "2") (pinfunction "2_2") (pintype "passive"))
      (node (ref "C56") (pin "2") (pinfunction "2_2") (pintype "passive"))
      (node (ref "C57") (pin "1") (pinfunction "1_1") (pintype "passive"))
      (node (ref "C6") (pin "2") (pinfunction "2_2") (pintype "passive"))
      (node (ref "C61") (pin "1") (pinfunction "1_1") (pintype "passive"))
      (node (ref "C62") (pin "1") (pinfunction "1_1") (pintype "passive"))
      (node (ref "C63") (pin "1") (pinfunction "1_1") (pintype "passive"))
      (node (ref "C67") (pin "1") (pinfunction "1_1") (pintype "passive"))
      (node (ref "C68") (pin "1") (pinfunction "1_1") (pintype "passive"))
      (node (ref "C69") (pin "1") (pinfunction "1_1") (pintype "passive"))
      (node (ref "C70") (pin "1") (pinfunction "1_1") (pintype "passive"))
      (node (ref "C71") (pin "1") (pinfunction "1_1") (pintype "passive"))
      (node (ref "C73") (pin "1") (pinfunction "1_1") (pintype "passive"))
      (node (ref "C8") (pin "-") (pinfunction "-_-") (pintype "passive"))
      (node (ref "C9") (pin "-") (pinfunction "-_-") (pintype "passive"))
      (node (ref "IC1") (pin "13") (pinfunction "GND_13") (pintype "power_in"))
      (node (ref "IC1") (pin "14") (pinfunction "GND_14") (pintype "power_in"))
      (node (ref "IC1") (pin "9") (pinfunction "COM_9") (pintype "input"))
      (node (ref "IC2") (pin "13") (pinfunction "GND_13") (pintype "power_in"))
      (node (ref "IC2") (pin "14") (pinfunction "GND_14") (pintype "power_in"))
      (node (ref "IC2") (pin "9") (pinfunction "COM_9") (pintype "input"))
      (node (ref "R1") (pin "1") (pinfunction "1_1") (pintype "passive"))
      (node (ref "R12") (pin "1") (pinfunction "1_1") (pintype "passive"))
      (node (ref "R2") (pin "1") (pinfunction "1_1") (pintype "passive"))
      (node (ref "R7") (pin "1") (pinfunction "1_1") (pintype "passive"))
      (node (ref "R9") (pin "1") (pinfunction "1_1") (pintype "passive"))
      (node (ref "U$1") (pin "G10") (pinfunction "RES_10_G10") (pintype "bidirectional"))
      (node (ref "U$1") (pin "G11") (pinfunction "RES_11_G11") (pintype "bidirectional"))
      (node (ref "U$1") (pin "G12") (pinfunction "RES_12_G12") (pintype "bidirectional"))
      (node (ref "U$1") (pin "G13") (pinfunction "GND_G13") (pintype "bidirectional"))
      (node (ref "U$1") (pin "G4") (pinfunction "SDO/SA0_G4") (pintype "bidirectional"))
      (node (ref "U$1") (pin "G8") (pinfunction "RES_8_G8") (pintype "bidirectional"))
      (node (ref "U$1") (pin "G9") (pinfunction "RES_9_G9") (pintype "bidirectional"))
      (node (ref "U$2") (pin "G2") (pinfunction "ST_G2") (pintype "bidirectional"))
      (node (ref "U$2") (pin "G4") (pinfunction "GND_G4") (pintype "bidirectional"))
      (node (ref "U$2") (pin "G8") (pinfunction "SLEEP/PD_G8") (pintype "bidirectional"))
      (node (ref "U$3") (pin "P$2") (pinfunction "GND_P$2") (pintype "bidirectional"))
      (node (ref "U$4") (pin "G10") (pinfunction "RES_10_G10") (pintype "bidirectional"))
      (node (ref "U$4") (pin "G11") (pinfunction "RES_11_G11") (pintype "bidirectional"))
      (node (ref "U$4") (pin "G12") (pinfunction "RES_12_G12") (pintype "bidirectional"))
      (node (ref "U$4") (pin "G13") (pinfunction "GND_G13") (pintype "bidirectional"))
      (node (ref "U$4") (pin "G8") (pinfunction "RES_8_G8") (pintype "bidirectional"))
      (node (ref "U$4") (pin "G9") (pinfunction "RES_9_G9") (pintype "bidirectional"))
      (node (ref "U$5") (pin "G2") (pinfunction "ST_G2") (pintype "bidirectional"))
      (node (ref "U$5") (pin "G4") (pinfunction "GND_G4") (pintype "bidirectional"))
      (node (ref "U$5") (pin "G8") (pinfunction "SLEEP/PD_G8") (pintype "bidirectional"))
      (node (ref "U1") (pin "18") (pinfunction "GND_2_18") (pintype "passive"))
      (node (ref "U1") (pin "19") (pinfunction "GND_19") (pintype "passive"))
      (node (ref "U2") (pin "10") (pinfunction "RSVD_2_10") (pintype "passive"))
      (node (ref "U2") (pin "11") (pinfunction "AVSS_11") (pintype "passive"))
      (node (ref "U2") (pin "12") (pinfunction "RSVD_3_12") (pintype "passive"))
      (node (ref "U2") (pin "13") (pinfunction "DVSS_13") (pintype "passive"))
      (node (ref "U2") (pin "2") (pinfunction "RSVD_4_2") (pintype "passive"))
      (node (ref "U2") (pin "3") (pinfunction "RSVD_3") (pintype "passive"))
      (node (ref "U2") (pin "7") (pinfunction "PSS_7") (pintype "passive"))
      (node (ref "U3") (pin "F1") (pinfunction "AGND_2_F1") (pintype "passive"))
      (node (ref "U3") (pin "F4") (pinfunction "ST2_2_F4") (pintype "passive"))
      (node (ref "U3") (pin "F5") (pinfunction "ST1_2_F5") (pintype "passive"))
      (node (ref "U3") (pin "F7") (pinfunction "PGND_F7") (pintype "passive"))
      (node (ref "U3") (pin "G2") (pinfunction "AGND_G2") (pintype "passive"))
      (node (ref "U3") (pin "G4") (pinfunction "ST2_G4") (pintype "passive"))
      (node (ref "U3") (pin "G5") (pinfunction "ST1_G5") (pintype "passive"))
      (node (ref "U3") (pin "G6") (pinfunction "PGND_2_G6") (pintype "passive"))
      (node (ref "U4") (pin "F1") (pinfunction "AGND_F1") (pintype "passive"))
      (node (ref "U4") (pin "F4") (pinfunction "ST2_F4") (pintype "passive"))
      (node (ref "U4") (pin "F5") (pinfunction "ST1_F5") (pintype "passive"))
      (node (ref "U4") (pin "F7") (pinfunction "PGND_2_F7") (pintype "passive"))
      (node (ref "U4") (pin "G2") (pinfunction "AGND_2_G2") (pintype "passive"))
      (node (ref "U4") (pin "G4") (pinfunction "ST2_2_G4") (pintype "passive"))
      (node (ref "U4") (pin "G5") (pinfunction "ST1_2_G5") (pintype "passive"))
      (node (ref "U4") (pin "G6") (pinfunction "PGND_G6") (pintype "passive"))
      (node (ref "U6") (pin "F1") (pinfunction "AGND_F1") (pintype "passive"))
      (node (ref "U6") (pin "F4") (pinfunction "ST2_F4") (pintype "passive"))
      (node (ref "U6") (pin "F5") (pinfunction "ST1_F5") (pintype "passive"))
      (node (ref "U6") (pin "F7") (pinfunction "PGND_2_F7") (pintype "passive"))
      (node (ref "U6") (pin "G2") (pinfunction "AGND_2_G2") (pintype "passive"))
      (node (ref "U6") (pin "G4") (pinfunction "ST2_2_G4") (pintype "passive"))
      (node (ref "U6") (pin "G5") (pinfunction "ST1_2_G5") (pintype "passive"))
      (node (ref "U6") (pin "G6") (pinfunction "PGND_G6") (pintype "passive"))
      (node (ref "U7") (pin "F1") (pinfunction "AGND_F1") (pintype "passive"))
      (node (ref "U7") (pin "F4") (pinfunction "ST2_F4") (pintype "passive"))
      (node (ref "U7") (pin "F5") (pinfunction "ST1_F5") (pintype "passive"))
      (node (ref "U7") (pin "F7") (pinfunction "PGND_2_F7") (pintype "passive"))
      (node (ref "U7") (pin "G2") (pinfunction "AGND_2_G2") (pintype "passive"))
      (node (ref "U7") (pin "G4") (pinfunction "ST2_2_G4") (pintype "passive"))
      (node (ref "U7") (pin "G5") (pinfunction "ST1_2_G5") (pintype "passive"))
      (node (ref "U7") (pin "G6") (pinfunction "PGND_G6") (pintype "passive"))
      (node (ref "U8") (pin "1") (pinfunction "CLKIN_1") (pintype "bidirectional"))
      (node (ref "U8") (pin "11") (pinfunction "FSYNC_11") (pintype "bidirectional"))
      (node (ref "U8") (pin "18") (pinfunction "GND_18") (pintype "bidirectional"))
      (node (ref "U9") (pin "GND@0") (pinfunction "GND_GND@0") (pintype "bidirectional"))
      (node (ref "U9") (pin "GND@1") (pinfunction "GND_GND@1") (pintype "bidirectional"))
      (node (ref "U9") (pin "GND@2") (pinfunction "GND_GND@2") (pintype "bidirectional"))
    )
    (net (code "5") (name "MISO") (class "Default")
      (node (ref "IC1") (pin "15") (pinfunction "DOUT_15") (pintype "output"))
      (node (ref "IC2") (pin "15") (pinfunction "DOUT_15") (pintype "output"))
      (node (ref "U1") (pin "2") (pinfunction "DOUT_2") (pintype "passive"))
      (node (ref "U2") (pin "5") (pinfunction "MISO_5") (pintype "passive"))
      (node (ref "U9") (pin "D12") (pinfunction "D12_D12") (pintype "bidirectional"))
    )
    (net (code "6") (name "MOSI") (class "Default")
      (node (ref "IC1") (pin "17") (pinfunction "DI_17") (pintype "input"))
      (node (ref "IC2") (pin "17") (pinfunction "DI_17") (pintype "input"))
      (node (ref "U1") (pin "3") (pinfunction "DIN_3") (pintype "passive"))
      (node (ref "U2") (pin "15") (pinfunction "MOSI_15") (pintype "passive"))
      (node (ref "U9") (pin "D11") (pinfunction "*D11_D11") (pintype "bidirectional"))
    )
    (net (code "7") (name "N$56") (class "Default")
      (node (ref "R23") (pin "2") (pinfunction "2_2") (pintype "passive"))
    )
    (net (code "8") (name "N$57") (class "Default")
      (node (ref "R28") (pin "2") (pinfunction "2_2") (pintype "passive"))
    )
    (net (code "9") (name "N$58") (class "Default")
      (node (ref "R24") (pin "1") (pinfunction "1_1") (pintype "passive"))
    )
    (net (code "10") (name "N$59") (class "Default")
      (node (ref "R26") (pin "1") (pinfunction "1_1") (pintype "passive"))
    )
    (net (code "11") (name "N$60") (class "Default")
      (node (ref "R25") (pin "1") (pinfunction "1_1") (pintype "passive"))
    )
    (net (code "12") (name "N$61") (class "Default")
      (node (ref "R27") (pin "1") (pinfunction "1_1") (pintype "passive"))
    )
    (net (code "13") (name "Net-(C7-Pad2)") (class "Default")
      (node (ref "C7") (pin "2") (pinfunction "2_2") (pintype "passive"))
      (node (ref "R1") (pin "2") (pinfunction "2_2") (pintype "passive"))
    )
    (net (code "14") (name "Net-(C11-Pad1)") (class "Default")
      (node (ref "C11") (pin "1") (pinfunction "1_1") (pintype "passive"))
      (node (ref "R2") (pin "2") (pinfunction "2_2") (pintype "passive"))
    )
    (net (code "15") (name "Net-(C24-Pad1)") (class "Default")
      (node (ref "C24") (pin "1") (pinfunction "1_1") (pintype "passive"))
      (node (ref "R9") (pin "2") (pinfunction "2_2") (pintype "passive"))
    )
    (net (code "16") (name "Net-(C26-Pad2)") (class "Default")
      (node (ref "C26") (pin "2") (pinfunction "2_2") (pintype "passive"))
      (node (ref "R12") (pin "2") (pinfunction "2_2") (pintype "passive"))
    )
    (net (code "17") (name "Net-(IC1-CH0)") (class "Default")
      (node (ref "C37") (pin "2") (pinfunction "2_2") (pintype "passive"))
      (node (ref "IC1") (pin "1") (pinfunction "CH0_1") (pintype "input"))
      (node (ref "R13") (pin "1") (pinfunction "1_1") (pintype "passive"))
    )
    (net (code "18") (name "Net-(IC1-CH1)") (class "Default")
      (node (ref "C41") (pin "2") (pinfunction "2_2") (pintype "passive"))
      (node (ref "IC1") (pin "2") (pinfunction "CH1_2") (pintype "input"))
      (node (ref "R14") (pin "1") (pinfunction "1_1") (pintype "passive"))
    )
    (net (code "19") (name "Net-(IC1-CH2)") (class "Default")
      (node (ref "C42") (pin "2") (pinfunction "2_2") (pintype "passive"))
      (node (ref "IC1") (pin "3") (pinfunction "CH2_3") (pintype "input"))
      (node (ref "R15") (pin "1") (pinfunction "1_1") (pintype "passive"))
    )
    (net (code "20") (name "Net-(IC1-CH3)") (class "Default")
      (node (ref "C47") (pin "2") (pinfunction "2_2") (pintype "passive"))
      (node (ref "IC1") (pin "4") (pinfunction "CH3_4") (pintype "input"))
      (node (ref "R20") (pin "1") (pinfunction "1_1") (pintype "passive"))
    )
    (net (code "21") (name "Net-(IC1-CH4)") (class "Default")
      (node (ref "C46") (pin "1") (pinfunction "1_1") (pintype "passive"))
      (node (ref "IC1") (pin "5") (pinfunction "CH4_5") (pintype "input"))
      (node (ref "R19") (pin "2") (pinfunction "2_2") (pintype "passive"))
    )
    (net (code "22") (name "Net-(IC1-CH5)") (class "Default")
      (node (ref "C45") (pin "1") (pinfunction "1_1") (pintype "passive"))
      (node (ref "IC1") (pin "6") (pinfunction "CH5_6") (pintype "input"))
      (node (ref "R18") (pin "2") (pinfunction "2_2") (pintype "passive"))
    )
    (net (code "23") (name "Net-(IC1-CH6)") (class "Default")
      (node (ref "C44") (pin "1") (pinfunction "1_1") (pintype "passive"))
      (node (ref "IC1") (pin "7") (pinfunction "CH6_7") (pintype "input"))
      (node (ref "R17") (pin "2") (pinfunction "2_2") (pintype "passive"))
    )
    (net (code "24") (name "Net-(IC1-CH7)") (class "Default")
      (node (ref "C43") (pin "1") (pinfunction "1_1") (pintype "passive"))
      (node (ref "IC1") (pin "8") (pinfunction "CH7_8") (pintype "input"))
      (node (ref "R16") (pin "2") (pinfunction "2_2") (pintype "passive"))
    )
    (net (code "25") (name "Net-(IC2-CH0)") (class "Default")
      (node (ref "C50") (pin "2") (pinfunction "2_2") (pintype "passive"))
      (node (ref "IC2") (pin "1") (pinfunction "CH0_1") (pintype "input"))
      (node (ref "R21") (pin "1") (pinfunction "1_1") (pintype "passive"))
    )
    (net (code "26") (name "Net-(IC2-CH1)") (class "Default")
      (node (ref "C51") (pin "2") (pinfunction "2_2") (pintype "passive"))
      (node (ref "IC2") (pin "2") (pinfunction "CH1_2") (pintype "input"))
      (node (ref "R22") (pin "1") (pinfunction "1_1") (pintype "passive"))
    )
    (net (code "27") (name "Net-(IC2-CH2)") (class "Default")
      (node (ref "C52") (pin "2") (pinfunction "2_2") (pintype "passive"))
      (node (ref "IC2") (pin "3") (pinfunction "CH2_3") (pintype "input"))
      (node (ref "R23") (pin "1") (pinfunction "1_1") (pintype "passive"))
    )
    (net (code "28") (name "Net-(IC2-CH3)") (class "Default")
      (node (ref "C57") (pin "2") (pinfunction "2_2") (pintype "passive"))
      (node (ref "IC2") (pin "4") (pinfunction "CH3_4") (pintype "input"))
      (node (ref "R28") (pin "1") (pinfunction "1_1") (pintype "passive"))
    )
    (net (code "29") (name "Net-(IC2-CH4)") (class "Default")
      (node (ref "C56") (pin "1") (pinfunction "1_1") (pintype "passive"))
      (node (ref "IC2") (pin "5") (pinfunction "CH4_5") (pintype "input"))
      (node (ref "R27") (pin "2") (pinfunction "2_2") (pintype "passive"))
    )
    (net (code "30") (name "Net-(IC2-CH5)") (class "Default")
      (node (ref "C55") (pin "1") (pinfunction "1_1") (pintype "passive"))
      (node (ref "IC2") (pin "6") (pinfunction "CH5_6") (pintype "input"))
      (node (ref "R25") (pin "2") (pinfunction "2_2") (pintype "passive"))
    )
    (net (code "31") (name "Net-(IC2-CH6)") (class "Default")
      (node (ref "C54") (pin "1") (pinfunction "1_1") (pintype "passive"))
      (node (ref "IC2") (pin "7") (pinfunction "CH6_7") (pintype "input"))
      (node (ref "R26") (pin "2") (pinfunction "2_2") (pintype "passive"))
    )
    (net (code "32") (name "Net-(IC2-CH7)") (class "Default")
      (node (ref "C53") (pin "1") (pinfunction "1_1") (pintype "passive"))
      (node (ref "IC2") (pin "8") (pinfunction "CH7_8") (pintype "input"))
      (node (ref "R24") (pin "2") (pinfunction "2_2") (pintype "passive"))
    )
    (net (code "33") (name "Net-(U$1-PLLFILT)") (class "Default")
      (node (ref "C10") (pin "2") (pinfunction "2_2") (pintype "passive"))
      (node (ref "C11") (pin "2") (pinfunction "2_2") (pintype "passive"))
      (node (ref "U$1") (pin "G14") (pinfunction "PLLFILT_G14") (pintype "bidirectional"))
    )
    (net (code "34") (name "Net-(U$2-VCONT)") (class "Default")
      (node (ref "C6") (pin "1") (pinfunction "1_1") (pintype "passive"))
      (node (ref "C7") (pin "1") (pinfunction "1_1") (pintype "passive"))
      (node (ref "U$2") (pin "G3") (pinfunction "VCONT_G3") (pintype "bidirectional"))
    )
    (net (code "35") (name "Net-(U$3-FB)") (class "Default")
      (node (ref "C22") (pin "2") (pinfunction "2_2") (pintype "passive"))
      (node (ref "R7") (pin "2") (pinfunction "2_2") (pintype "passive"))
      (node (ref "R8") (pin "1") (pinfunction "1_1") (pintype "passive"))
      (node (ref "U$3") (pin "P$3") (pinfunction "FB_P$3") (pintype "bidirectional"))
    )
    (net (code "36") (name "Net-(U$3-SW)") (class "Default")
      (node (ref "D1") (pin "A") (pinfunction "A_A") (pintype "passive"))
      (node (ref "L1") (pin "2") (pinfunction "2_2") (pintype "passive"))
      (node (ref "U$3") (pin "P$1") (pinfunction "SW_P$1") (pintype "bidirectional"))
    )
    (net (code "37") (name "Net-(U$4-PLLFILT)") (class "Default")
      (node (ref "C23") (pin "2") (pinfunction "2_2") (pintype "passive"))
      (node (ref "C24") (pin "2") (pinfunction "2_2") (pintype "passive"))
      (node (ref "U$4") (pin "G14") (pinfunction "PLLFILT_G14") (pintype "bidirectional"))
    )
    (net (code "38") (name "Net-(U$5-VCONT)") (class "Default")
      (node (ref "C25") (pin "1") (pinfunction "1_1") (pintype "passive"))
      (node (ref "C26") (pin "1") (pinfunction "1_1") (pintype "passive"))
      (node (ref "U$5") (pin "G3") (pinfunction "VCONT_G3") (pintype "bidirectional"))
    )
    (net (code "39") (name "Net-(U2-AVDD)") (class "Default")
      (node (ref "C1") (pin "2") (pinfunction "2_2") (pintype "passive"))
      (node (ref "U2") (pin "14") (pinfunction "AVDD_14") (pintype "passive"))
    )
    (net (code "40") (name "Net-(U2-CPS)") (class "Default")
      (node (ref "C4") (pin "2") (pinfunction "2_2") (pintype "passive"))
      (node (ref "D2") (pin "C") (pinfunction "C_C") (pintype "passive"))
      (node (ref "U2") (pin "9") (pinfunction "CPS_9") (pintype "passive"))
    )
    (net (code "41") (name "Net-(U2-DVDD)") (class "Default")
      (node (ref "C2") (pin "2") (pinfunction "2_2") (pintype "passive"))
      (node (ref "U2") (pin "1") (pinfunction "DVDD_1") (pintype "passive"))
    )
    (net (code "42") (name "Net-(U2-VX)") (class "Default")
      (node (ref "D2") (pin "A") (pinfunction "A_A") (pintype "passive"))
      (node (ref "L3") (pin "2") (pinfunction "2_2") (pintype "passive"))
      (node (ref "U2") (pin "8") (pinfunction "VX_8") (pintype "passive"))
    )
    (net (code "43") (name "Net-(U3-CP1)") (class "Default")
      (node (ref "C12") (pin "2") (pinfunction "2_2") (pintype "passive"))
      (node (ref "U3") (pin "A5") (pinfunction "CP1_2_A5") (pintype "passive"))
      (node (ref "U3") (pin "B5") (pinfunction "CP1_B5") (pintype "passive"))
    )
    (net (code "44") (name "Net-(U3-CP2)") (class "Default")
      (node (ref "C12") (pin "1") (pinfunction "1_1") (pintype "passive"))
      (node (ref "U3") (pin "A4") (pinfunction "CP2_2_A4") (pintype "passive"))
      (node (ref "U3") (pin "B4") (pinfunction "CP2_B4") (pintype "passive"))
    )
    (net (code "45") (name "Net-(U3-CP3)") (class "Default")
      (node (ref "C13") (pin "1") (pinfunction "1_1") (pintype "passive"))
      (node (ref "U3") (pin "C6") (pinfunction "CP3_2_C6") (pintype "passive"))
      (node (ref "U3") (pin "C7") (pinfunction "CP3_C7") (pintype "passive"))
    )
    (net (code "46") (name "Net-(U3-CP4)") (class "Default")
      (node (ref "C13") (pin "2") (pinfunction "2_2") (pintype "passive"))
      (node (ref "U3") (pin "A6") (pinfunction "CP4_2_A6") (pintype "passive"))
      (node (ref "U3") (pin "B7") (pinfunction "CP4_B7") (pintype "passive"))
    )
    (net (code "47") (name "Net-(U3-CP5)") (class "Default")
      (node (ref "C16") (pin "2") (pinfunction "2_2") (pintype "passive"))
      (node (ref "U3") (pin "D6") (pinfunction "CP5_2_D6") (pintype "passive"))
      (node (ref "U3") (pin "D7") (pinfunction "CP5_D7") (pintype "passive"))
    )
    (net (code "48") (name "Net-(U3-SUMJ)") (class "Default")
      (node (ref "C14") (pin "1") (pinfunction "1_1") (pintype "passive"))
      (node (ref "U3") (pin "C1") (pinfunction "SUMJ_C1") (pintype "passive"))
      (node (ref "U3") (pin "C2") (pinfunction "SUMJ_2_C2") (pintype "passive"))
    )
    (net (code "49") (name "Net-(U4-CP1)") (class "Default")
      (node (ref "C27") (pin "2") (pinfunction "2_2") (pintype "passive"))
      (node (ref "U4") (pin "A5") (pinfunction "CP1_A5") (pintype "passive"))
      (node (ref "U4") (pin "B5") (pinfunction "CP1_2_B5") (pintype "passive"))
    )
    (net (code "50") (name "Net-(U4-CP2)") (class "Default")
      (node (ref "C27") (pin "1") (pinfunction "1_1") (pintype "passive"))
      (node (ref "U4") (pin "A4") (pinfunction "CP2_A4") (pintype "passive"))
      (node (ref "U4") (pin "B4") (pinfunction "CP2_2_B4") (pintype "passive"))
    )
    (net (code "51") (name "Net-(U4-CP3)") (class "Default")
      (node (ref "C28") (pin "1") (pinfunction "1_1") (pintype "passive"))
      (node (ref "U4") (pin "C6") (pinfunction "CP3_C6") (pintype "passive"))
      (node (ref "U4") (pin "C7") (pinfunction "CP3_2_C7") (pintype "passive"))
    )
    (net (code "52") (name "Net-(U4-CP4)") (class "Default")
      (node (ref "C28") (pin "2") (pinfunction "2_2") (pintype "passive"))
      (node (ref "U4") (pin "A6") (pinfunction "CP4_A6") (pintype "passive"))
      (node (ref "U4") (pin "B7") (pinfunction "CP4_2_B7") (pintype "passive"))
    )
    (net (code "53") (name "Net-(U4-CP5)") (class "Default")
      (node (ref "C30") (pin "2") (pinfunction "2_2") (pintype "passive"))
      (node (ref "U4") (pin "D6") (pinfunction "CP5_D6") (pintype "passive"))
      (node (ref "U4") (pin "D7") (pinfunction "CP5_2_D7") (pintype "passive"))
    )
    (net (code "54") (name "Net-(U4-SUMJ)") (class "Default")
      (node (ref "C29") (pin "1") (pinfunction "1_1") (pintype "passive"))
      (node (ref "U4") (pin "C1") (pinfunction "SUMJ_C1") (pintype "passive"))
      (node (ref "U4") (pin "C2") (pinfunction "SUMJ_2_C2") (pintype "passive"))
    )
    (net (code "55") (name "Net-(U6-CP1)") (class "Default")
      (node (ref "C58") (pin "2") (pinfunction "2_2") (pintype "passive"))
      (node (ref "U6") (pin "A5") (pinfunction "CP1_A5") (pintype "passive"))
      (node (ref "U6") (pin "B5") (pinfunction "CP1_2_B5") (pintype "passive"))
    )
    (net (code "56") (name "Net-(U6-CP2)") (class "Default")
      (node (ref "C58") (pin "1") (pinfunction "1_1") (pintype "passive"))
      (node (ref "U6") (pin "A4") (pinfunction "CP2_A4") (pintype "passive"))
      (node (ref "U6") (pin "B4") (pinfunction "CP2_2_B4") (pintype "passive"))
    )
    (net (code "57") (name "Net-(U6-CP3)") (class "Default")
      (node (ref "C59") (pin "1") (pinfunction "1_1") (pintype "passive"))
      (node (ref "U6") (pin "C6") (pinfunction "CP3_C6") (pintype "passive"))
      (node (ref "U6") (pin "C7") (pinfunction "CP3_2_C7") (pintype "passive"))
    )
    (net (code "58") (name "Net-(U6-CP4)") (class "Default")
      (node (ref "C59") (pin "2") (pinfunction "2_2") (pintype "passive"))
      (node (ref "U6") (pin "A6") (pinfunction "CP4_A6") (pintype "passive"))
      (node (ref "U6") (pin "B7") (pinfunction "CP4_2_B7") (pintype "passive"))
    )
    (net (code "59") (name "Net-(U6-CP5)") (class "Default")
      (node (ref "C61") (pin "2") (pinfunction "2_2") (pintype "passive"))
      (node (ref "U6") (pin "D6") (pinfunction "CP5_D6") (pintype "passive"))
      (node (ref "U6") (pin "D7") (pinfunction "CP5_2_D7") (pintype "passive"))
    )
    (net (code "60") (name "Net-(U6-SUMJ)") (class "Default")
      (node (ref "C60") (pin "1") (pinfunction "1_1") (pintype "passive"))
      (node (ref "U6") (pin "C1") (pinfunction "SUMJ_C1") (pintype "passive"))
      (node (ref "U6") (pin "C2") (pinfunction "SUMJ_2_C2") (pintype "passive"))
    )
    (net (code "61") (name "Net-(U7-CP1)") (class "Default")
      (node (ref "C64") (pin "2") (pinfunction "2_2") (pintype "passive"))
      (node (ref "U7") (pin "A5") (pinfunction "CP1_A5") (pintype "passive"))
      (node (ref "U7") (pin "B5") (pinfunction "CP1_2_B5") (pintype "passive"))
    )
    (net (code "62") (name "Net-(U7-CP2)") (class "Default")
      (node (ref "C64") (pin "1") (pinfunction "1_1") (pintype "passive"))
      (node (ref "U7") (pin "A4") (pinfunction "CP2_A4") (pintype "passive"))
      (node (ref "U7") (pin "B4") (pinfunction "CP2_2_B4") (pintype "passive"))
    )
    (net (code "63") (name "Net-(U7-CP3)") (class "Default")
      (node (ref "C65") (pin "1") (pinfunction "1_1") (pintype "passive"))
      (node (ref "U7") (pin "C6") (pinfunction "CP3_C6") (pintype "passive"))
      (node (ref "U7") (pin "C7") (pinfunction "CP3_2_C7") (pintype "passive"))
    )
    (net (code "64") (name "Net-(U7-CP4)") (class "Default")
      (node (ref "C65") (pin "2") (pinfunction "2_2") (pintype "passive"))
      (node (ref "U7") (pin "A6") (pinfunction "CP4_A6") (pintype "passive"))
      (node (ref "U7") (pin "B7") (pinfunction "CP4_2_B7") (pintype "passive"))
    )
    (net (code "65") (name "Net-(U7-CP5)") (class "Default")
      (node (ref "C67") (pin "2") (pinfunction "2_2") (pintype "passive"))
      (node (ref "U7") (pin "D6") (pinfunction "CP5_D6") (pintype "passive"))
      (node (ref "U7") (pin "D7") (pinfunction "CP5_2_D7") (pintype "passive"))
    )
    (net (code "66") (name "Net-(U7-SUMJ)") (class "Default")
      (node (ref "C66") (pin "1") (pinfunction "1_1") (pintype "passive"))
      (node (ref "U7") (pin "C1") (pinfunction "SUMJ_C1") (pintype "passive"))
      (node (ref "U7") (pin "C2") (pinfunction "SUMJ_2_C2") (pintype "passive"))
    )
    (net (code "67") (name "Net-(U8-CPOUT)") (class "Default")
      (node (ref "C71") (pin "2") (pinfunction "2_2") (pintype "passive"))
      (node (ref "U8") (pin "20") (pinfunction "CPOUT_20") (pintype "bidirectional"))
    )
    (net (code "68") (name "Net-(U8-REGOUT)") (class "Default")
      (node (ref "C70") (pin "2") (pinfunction "2_2") (pintype "passive"))
      (node (ref "U8") (pin "10") (pinfunction "REGOUT_10") (pintype "bidirectional"))
    )
    (net (code "69") (name "Net-(U8-VLOGIC)") (class "Default")
      (node (ref "C73") (pin "2") (pinfunction "2_2") (pintype "passive"))
      (node (ref "U8") (pin "8") (pinfunction "VLOGIC_8") (pintype "bidirectional"))
    )
    (net (code "70") (name "OUTZ_ADXRS622") (class "Default")
      (node (ref "C66") (pin "2") (pinfunction "2_2") (pintype "passive"))
      (node (ref "R15") (pin "2") (pinfunction "2_2") (pintype "passive"))
      (node (ref "U7") (pin "A2") (pinfunction "RATEOUT_2_A2") (pintype "passive"))
      (node (ref "U7") (pin "B1") (pinfunction "RATEOUT_B1") (pintype "passive"))
    )
    (net (code "71") (name "OUTZ_ADXRS642") (class "Default")
      (node (ref "C60") (pin "2") (pinfunction "2_2") (pintype "passive"))
      (node (ref "R19") (pin "1") (pinfunction "1_1") (pintype "passive"))
      (node (ref "U6") (pin "A2") (pinfunction "RATEOUT_2_A2") (pintype "passive"))
      (node (ref "U6") (pin "B1") (pinfunction "RATEOUT_B1") (pintype "passive"))
    )
    (net (code "72") (name "OUTZ_ADXRS646") (class "Default")
      (node (ref "C14") (pin "2") (pinfunction "2_2") (pintype "passive"))
      (node (ref "R13") (pin "2") (pinfunction "2_2") (pintype "passive"))
      (node (ref "U3") (pin "A2") (pinfunction "RATEOUT_2_A2") (pintype "passive"))
      (node (ref "U3") (pin "B1") (pinfunction "RATEOUT_B1") (pintype "passive"))
    )
    (net (code "73") (name "OUTZ_ADXRS652") (class "Default")
      (node (ref "C29") (pin "2") (pinfunction "2_2") (pintype "passive"))
      (node (ref "R17") (pin "1") (pinfunction "1_1") (pintype "passive"))
      (node (ref "U4") (pin "A2") (pinfunction "RATEOUT_2_A2") (pintype "passive"))
      (node (ref "U4") (pin "B1") (pinfunction "RATEOUT_B1") (pintype "passive"))
    )
    (net (code "74") (name "OUTZ_LY330") (class "Default")
      (node (ref "R21") (pin "2") (pinfunction "2_2") (pintype "passive"))
      (node (ref "U$2") (pin "G6") (pinfunction "OUTZ_G6") (pintype "bidirectional"))
    )
    (net (code "75") (name "OUTZ_LY3200") (class "Default")
      (node (ref "R22") (pin "2") (pinfunction "2_2") (pintype "passive"))
      (node (ref "U$5") (pin "G6") (pinfunction "OUTZ_G6") (pintype "bidirectional"))
    )
    (net (code "76") (name "SCLK") (class "Default")
      (node (ref "IC1") (pin "19") (pinfunction "DCLK_19") (pintype "input"))
      (node (ref "IC2") (pin "19") (pinfunction "DCLK_19") (pintype "input"))
      (node (ref "U1") (pin "1") (pinfunction "SCLK_1") (pintype "passive"))
      (node (ref "U2") (pin "16") (pinfunction "SCLK_16") (pintype "passive"))
      (node (ref "U9") (pin "D13") (pinfunction "D13_D13") (pintype "bidirectional"))
    )
    (net (code "77") (name "SCL_3.3V") (class "Default")
      (node (ref "Q2") (pin "2") (pinfunction "S_2") (pintype "passive"))
      (node (ref "R31") (pin "1") (pinfunction "1_1") (pintype "passive"))
      (node (ref "U$1") (pin "G2") (pinfunction "SPC/SCL_G2") (pintype "bidirectional"))
      (node (ref "U$4") (pin "G2") (pinfunction "SPC/SCL_G2") (pintype "bidirectional"))
      (node (ref "U8") (pin "23") (pinfunction "SCL_23") (pintype "bidirectional"))
    )
    (net (code "78") (name "SCL_5V") (class "Default")
      (node (ref "Q2") (pin "3") (pinfunction "D_3") (pintype "passive"))
      (node (ref "R32") (pin "1") (pinfunction "1_1") (pintype "passive"))
      (node (ref "U9") (pin "A5") (pinfunction "A5_A5") (pintype "bidirectional"))
    )
    (net (code "79") (name "SDA_3.3V") (class "Default")
      (node (ref "Q1") (pin "2") (pinfunction "S_2") (pintype "passive"))
      (node (ref "R5") (pin "1") (pinfunction "1_1") (pintype "passive"))
      (node (ref "U$1") (pin "G3") (pinfunction "SDA/SDI/SDO_G3") (pintype "bidirectional"))
      (node (ref "U$4") (pin "G3") (pinfunction "SDA/SDI/SDO_G3") (pintype "bidirectional"))
      (node (ref "U8") (pin "24") (pinfunction "SDA_24") (pintype "bidirectional"))
    )
    (net (code "80") (name "SDA_5V") (class "Default")
      (node (ref "Q1") (pin "3") (pinfunction "D_3") (pintype "passive"))
      (node (ref "R6") (pin "1") (pinfunction "1_1") (pintype "passive"))
      (node (ref "U9") (pin "A4") (pinfunction "A4_A4") (pintype "bidirectional"))
    )
    (net (code "81") (name "TEMP_ADXRS622") (class "Default")
      (node (ref "R20") (pin "2") (pinfunction "2_2") (pintype "passive"))
      (node (ref "U7") (pin "F3") (pinfunction "TEMP_F3") (pintype "passive"))
      (node (ref "U7") (pin "G3") (pinfunction "TEMP_2_G3") (pintype "passive"))
    )
    (net (code "82") (name "TEMP_ADXRS642") (class "Default")
      (node (ref "R18") (pin "1") (pinfunction "1_1") (pintype "passive"))
      (node (ref "U6") (pin "F3") (pinfunction "TEMP_F3") (pintype "passive"))
      (node (ref "U6") (pin "G3") (pinfunction "TEMP_2_G3") (pintype "passive"))
    )
    (net (code "83") (name "TEMP_ADXRS646") (class "Default")
      (node (ref "R14") (pin "2") (pinfunction "2_2") (pintype "passive"))
      (node (ref "U3") (pin "F3") (pinfunction "TEMP_2_F3") (pintype "passive"))
      (node (ref "U3") (pin "G3") (pinfunction "TEMP_G3") (pintype "passive"))
    )
    (net (code "84") (name "TEMP_ADXRS652") (class "Default")
      (node (ref "R16") (pin "1") (pinfunction "1_1") (pintype "passive"))
      (node (ref "U4") (pin "F3") (pinfunction "TEMP_F3") (pintype "passive"))
      (node (ref "U4") (pin "G3") (pinfunction "TEMP_2_G3") (pintype "passive"))
    )
    (net (code "85") (name "unconnected-(IC1-BUSY-Pad16)") (class "Default")
      (node (ref "IC1") (pin "16") (pinfunction "BUSY_16") (pintype "output"))
    )
    (net (code "86") (name "unconnected-(IC2-BUSY-Pad16)") (class "Default")
      (node (ref "IC2") (pin "16") (pinfunction "BUSY_16") (pintype "output"))
    )
    (net (code "87") (name "unconnected-(U$1-DRDY{slash}INT2-PadG6)") (class "Default")
      (node (ref "U$1") (pin "G6") (pinfunction "DRDY/INT2_G6") (pintype "bidirectional"))
    )
    (net (code "88") (name "unconnected-(U$1-INT1-PadG7)") (class "Default")
      (node (ref "U$1") (pin "G7") (pinfunction "INT1_G7") (pintype "bidirectional"))
    )
    (net (code "89") (name "unconnected-(U$2-VREF-PadG7)") (class "Default")
      (node (ref "U$2") (pin "G7") (pinfunction "VREF_G7") (pintype "bidirectional"))
    )
    (net (code "90") (name "unconnected-(U$4-DRDY{slash}INT2-PadG6)") (class "Default")
      (node (ref "U$4") (pin "G6") (pinfunction "DRDY/INT2_G6") (pintype "bidirectional"))
    )
    (net (code "91") (name "unconnected-(U$4-INT1-PadG7)") (class "Default")
      (node (ref "U$4") (pin "G7") (pinfunction "INT1_G7") (pintype "bidirectional"))
    )
    (net (code "92") (name "unconnected-(U$5-VREF-PadG7)") (class "Default")
      (node (ref "U$5") (pin "G7") (pinfunction "VREF_G7") (pintype "bidirectional"))
    )
    (net (code "93") (name "unconnected-(U1-AUX_ADC-Pad13)") (class "Default")
      (node (ref "U1") (pin "13") (pinfunction "AUX_ADC_13") (pintype "passive"))
    )
    (net (code "94") (name "unconnected-(U1-AUX_DAC-Pad12)") (class "Default")
      (node (ref "U1") (pin "12") (pinfunction "AUX_DAC_12") (pintype "passive"))
    )
    (net (code "95") (name "unconnected-(U1-DIO1-Pad5)") (class "Default")
      (node (ref "U1") (pin "5") (pinfunction "DIO1_5") (pintype "passive"))
    )
    (net (code "96") (name "unconnected-(U1-DIO2-Pad6)") (class "Default")
      (node (ref "U1") (pin "6") (pinfunction "DIO2_6") (pintype "passive"))
    )
    (net (code "97") (name "unconnected-(U1-DNC-Pad11)") (class "Default")
      (node (ref "U1") (pin "11") (pinfunction "DNC_11") (pintype "passive"))
    )
    (net (code "98") (name "unconnected-(U1-DNC_2-Pad8)") (class "Default")
      (node (ref "U1") (pin "8") (pinfunction "DNC_2_8") (pintype "passive"))
    )
    (net (code "99") (name "unconnected-(U1-DNC_3-Pad9)") (class "Default")
      (node (ref "U1") (pin "9") (pinfunction "DNC_3_9") (pintype "passive"))
    )
    (net (code "100") (name "unconnected-(U1-DNC_4-Pad10)") (class "Default")
      (node (ref "U1") (pin "10") (pinfunction "DNC_4_10") (pintype "passive"))
    )
    (net (code "101") (name "unconnected-(U1-FILT-Pad15)") (class "Default")
      (node (ref "U1") (pin "15") (pinfunction "FILT_15") (pintype "passive"))
    )
    (net (code "102") (name "unconnected-(U1-RATE-Pad14)") (class "Default")
      (node (ref "U1") (pin "14") (pinfunction "RATE_14") (pintype "passive"))
    )
    (net (code "103") (name "unconnected-(U1-VREF-Pad20)") (class "Default")
      (node (ref "U1") (pin "20") (pinfunction "VREF_20") (pintype "passive"))
    )
    (net (code "104") (name "unconnected-(U3-NC-PadD1)") (class "Default")
      (node (ref "U3") (pin "D1") (pinfunction "NC_D1") (pintype "passive"))
    )
    (net (code "105") (name "unconnected-(U3-NC_2-PadD2)") (class "Default")
      (node (ref "U3") (pin "D2") (pinfunction "NC_2_D2") (pintype "passive"))
    )
    (net (code "106") (name "unconnected-(U4-NC-PadD1)") (class "Default")
      (node (ref "U4") (pin "D1") (pinfunction "NC_D1") (pintype "passive"))
    )
    (net (code "107") (name "unconnected-(U4-NC_2-PadD2)") (class "Default")
      (node (ref "U4") (pin "D2") (pinfunction "NC_2_D2") (pintype "passive"))
    )
    (net (code "108") (name "unconnected-(U6-NC-PadD1)") (class "Default")
      (node (ref "U6") (pin "D1") (pinfunction "NC_D1") (pintype "passive"))
    )
    (net (code "109") (name "unconnected-(U6-NC_2-PadD2)") (class "Default")
      (node (ref "U6") (pin "D2") (pinfunction "NC_2_D2") (pintype "passive"))
    )
    (net (code "110") (name "unconnected-(U7-NC-PadD1)") (class "Default")
      (node (ref "U7") (pin "D1") (pinfunction "NC_D1") (pintype "passive"))
    )
    (net (code "111") (name "unconnected-(U7-NC_2-PadD2)") (class "Default")
      (node (ref "U7") (pin "D2") (pinfunction "NC_2_D2") (pintype "passive"))
    )
    (net (code "112") (name "unconnected-(U8-AUX_CL-Pad7)") (class "Default")
      (node (ref "U8") (pin "7") (pinfunction "AUX_CL_7") (pintype "bidirectional"))
    )
    (net (code "113") (name "unconnected-(U8-AUX_DA-Pad6)") (class "Default")
      (node (ref "U8") (pin "6") (pinfunction "AUX_DA_6") (pintype "bidirectional"))
    )
    (net (code "114") (name "unconnected-(U8-INT-Pad12)") (class "Default")
      (node (ref "U8") (pin "12") (pinfunction "INT_12") (pintype "bidirectional"))
    )
    (net (code "115") (name "unconnected-(U9-*D3-PadD3)") (class "Default")
      (node (ref "U9") (pin "D3") (pinfunction "*D3_D3") (pintype "bidirectional"))
    )
    (net (code "116") (name "unconnected-(U9-*D5-PadD5)") (class "Default")
      (node (ref "U9") (pin "D5") (pinfunction "*D5_D5") (pintype "bidirectional"))
    )
    (net (code "117") (name "unconnected-(U9-*D10-PadD10)") (class "Default")
      (node (ref "U9") (pin "D10") (pinfunction "*D10_D10") (pintype "bidirectional"))
    )
    (net (code "118") (name "unconnected-(U9-PadA0)") (class "Default")
      (node (ref "U9") (pin "A0") (pinfunction "A0_A0") (pintype "bidirectional"))
    )
    (net (code "119") (name "unconnected-(U9-PadA1)") (class "Default")
      (node (ref "U9") (pin "A1") (pinfunction "A1_A1") (pintype "bidirectional"))
    )
    (net (code "120") (name "unconnected-(U9-PadA2)") (class "Default")
      (node (ref "U9") (pin "A2") (pinfunction "A2_A2") (pintype "bidirectional"))
    )
    (net (code "121") (name "unconnected-(U9-PadA3)") (class "Default")
      (node (ref "U9") (pin "A3") (pinfunction "A3_A3") (pintype "bidirectional"))
    )
    (net (code "122") (name "unconnected-(U9-PadAREF)") (class "Default")
      (node (ref "U9") (pin "AREF") (pinfunction "AREF_AREF") (pintype "bidirectional"))
    )
    (net (code "123") (name "unconnected-(U9-PadD2)") (class "Default")
      (node (ref "U9") (pin "D2") (pinfunction "D2_D2") (pintype "bidirectional"))
    )
    (net (code "124") (name "unconnected-(U9-PadD4)") (class "Default")
      (node (ref "U9") (pin "D4") (pinfunction "D4_D4") (pintype "bidirectional"))
    )
    (net (code "125") (name "unconnected-(U9-PadRES)") (class "Default")
      (node (ref "U9") (pin "RES") (pinfunction "RES_RES") (pintype "bidirectional"))
    )
    (net (code "126") (name "unconnected-(U9-PadRX)") (class "Default")
      (node (ref "U9") (pin "RX") (pinfunction "RX_RX") (pintype "bidirectional"))
    )
    (net (code "127") (name "unconnected-(U9-PadTX)") (class "Default")
      (node (ref "U9") (pin "TX") (pinfunction "TX_TX") (pintype "bidirectional"))
    )
    (net (code "128") (name "unconnected-(U9-PadVIN)") (class "Default")
      (node (ref "U9") (pin "VIN") (pinfunction "VIN_VIN") (pintype "bidirectional"))
    )
    (net (code "129") (name "~{CS_ADC1}") (class "Default")
      (node (ref "IC1") (pin "18") (pinfunction "~{CS}_18") (pintype "input"))
      (node (ref "U9") (pin "D8") (pinfunction "D8_D8") (pintype "bidirectional"))
    )
    (net (code "130") (name "~{CS_ADC2}") (class "Default")
      (node (ref "IC2") (pin "18") (pinfunction "~{CS}_18") (pintype "input"))
      (node (ref "U9") (pin "D9") (pinfunction "*D9_D9") (pintype "bidirectional"))
    )
    (net (code "131") (name "~{CS_ADIS}") (class "Default")
      (node (ref "U1") (pin "4") (pinfunction "*CS_4") (pintype "passive"))
      (node (ref "U9") (pin "D6") (pinfunction "*D6_D6") (pintype "bidirectional"))
    )
    (net (code "132") (name "~{CS_ADXRS}") (class "Default")
      (node (ref "U2") (pin "4") (pinfunction "*CS_4") (pintype "passive"))
      (node (ref "U9") (pin "D7") (pinfunction "D7_D7") (pintype "bidirectional"))
    )
  )
)
